# zx80_SD_12_smd_build006_1_STM32.net
KiCad netlist of a schematic drawn in EAGLE
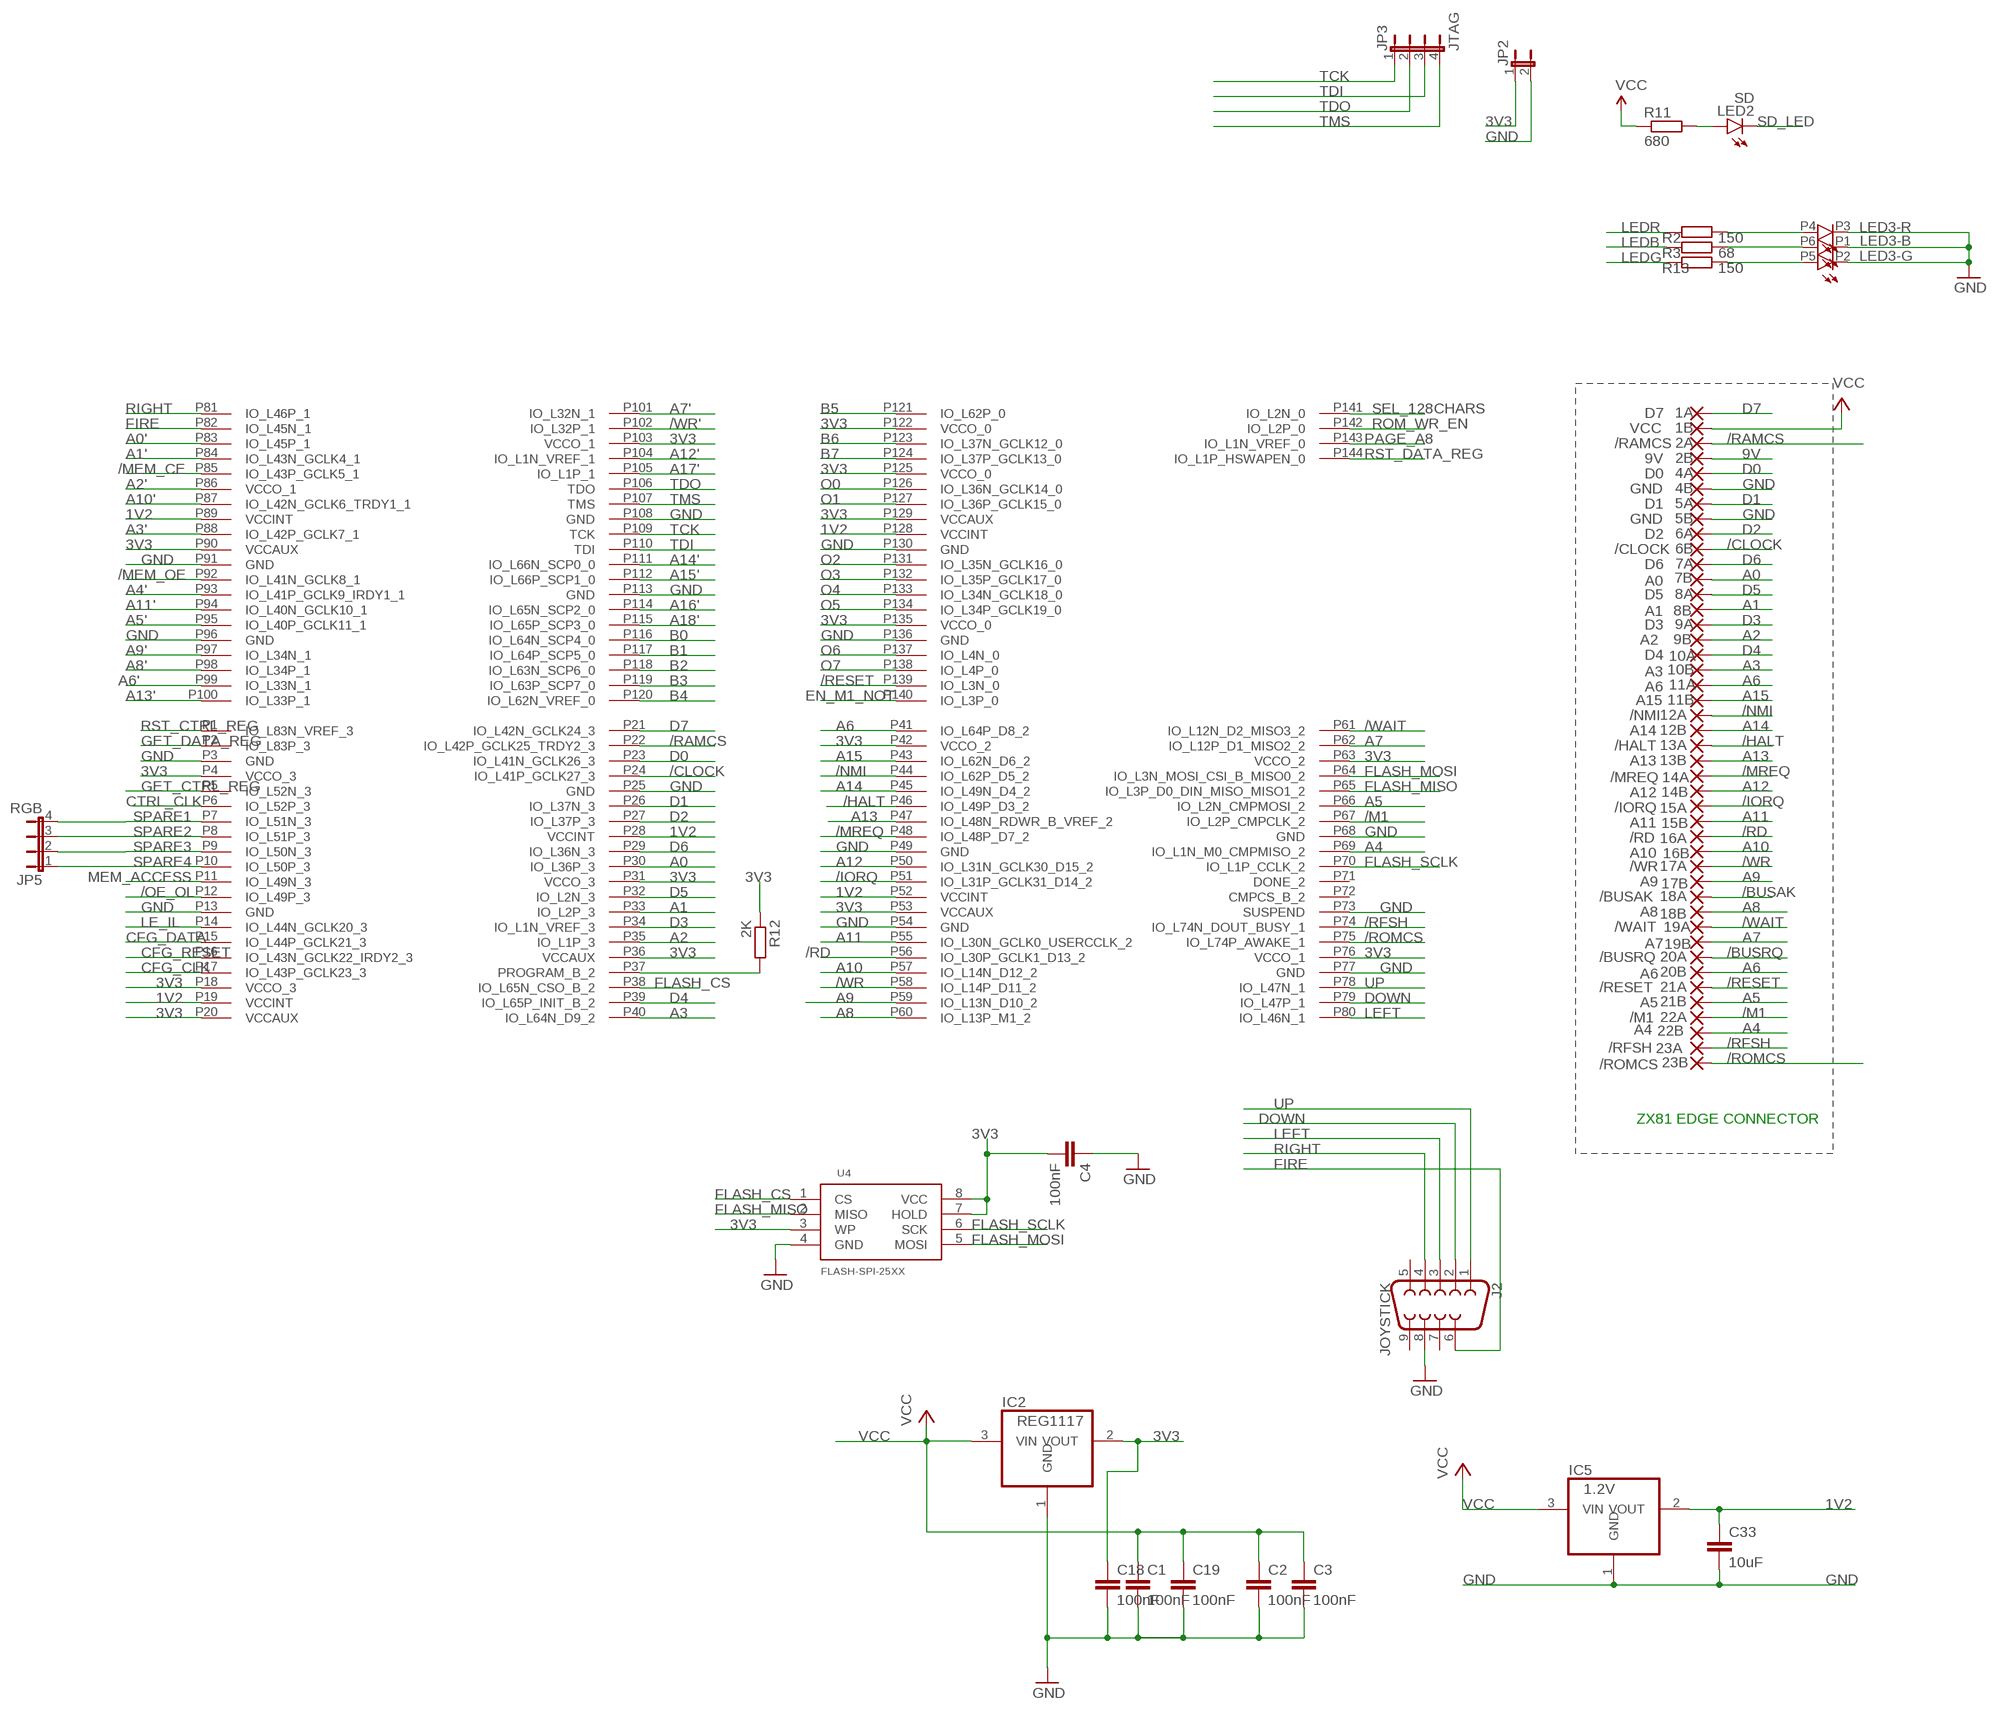
[diagram p0: schematic, sheet 1, part 1 of 2]
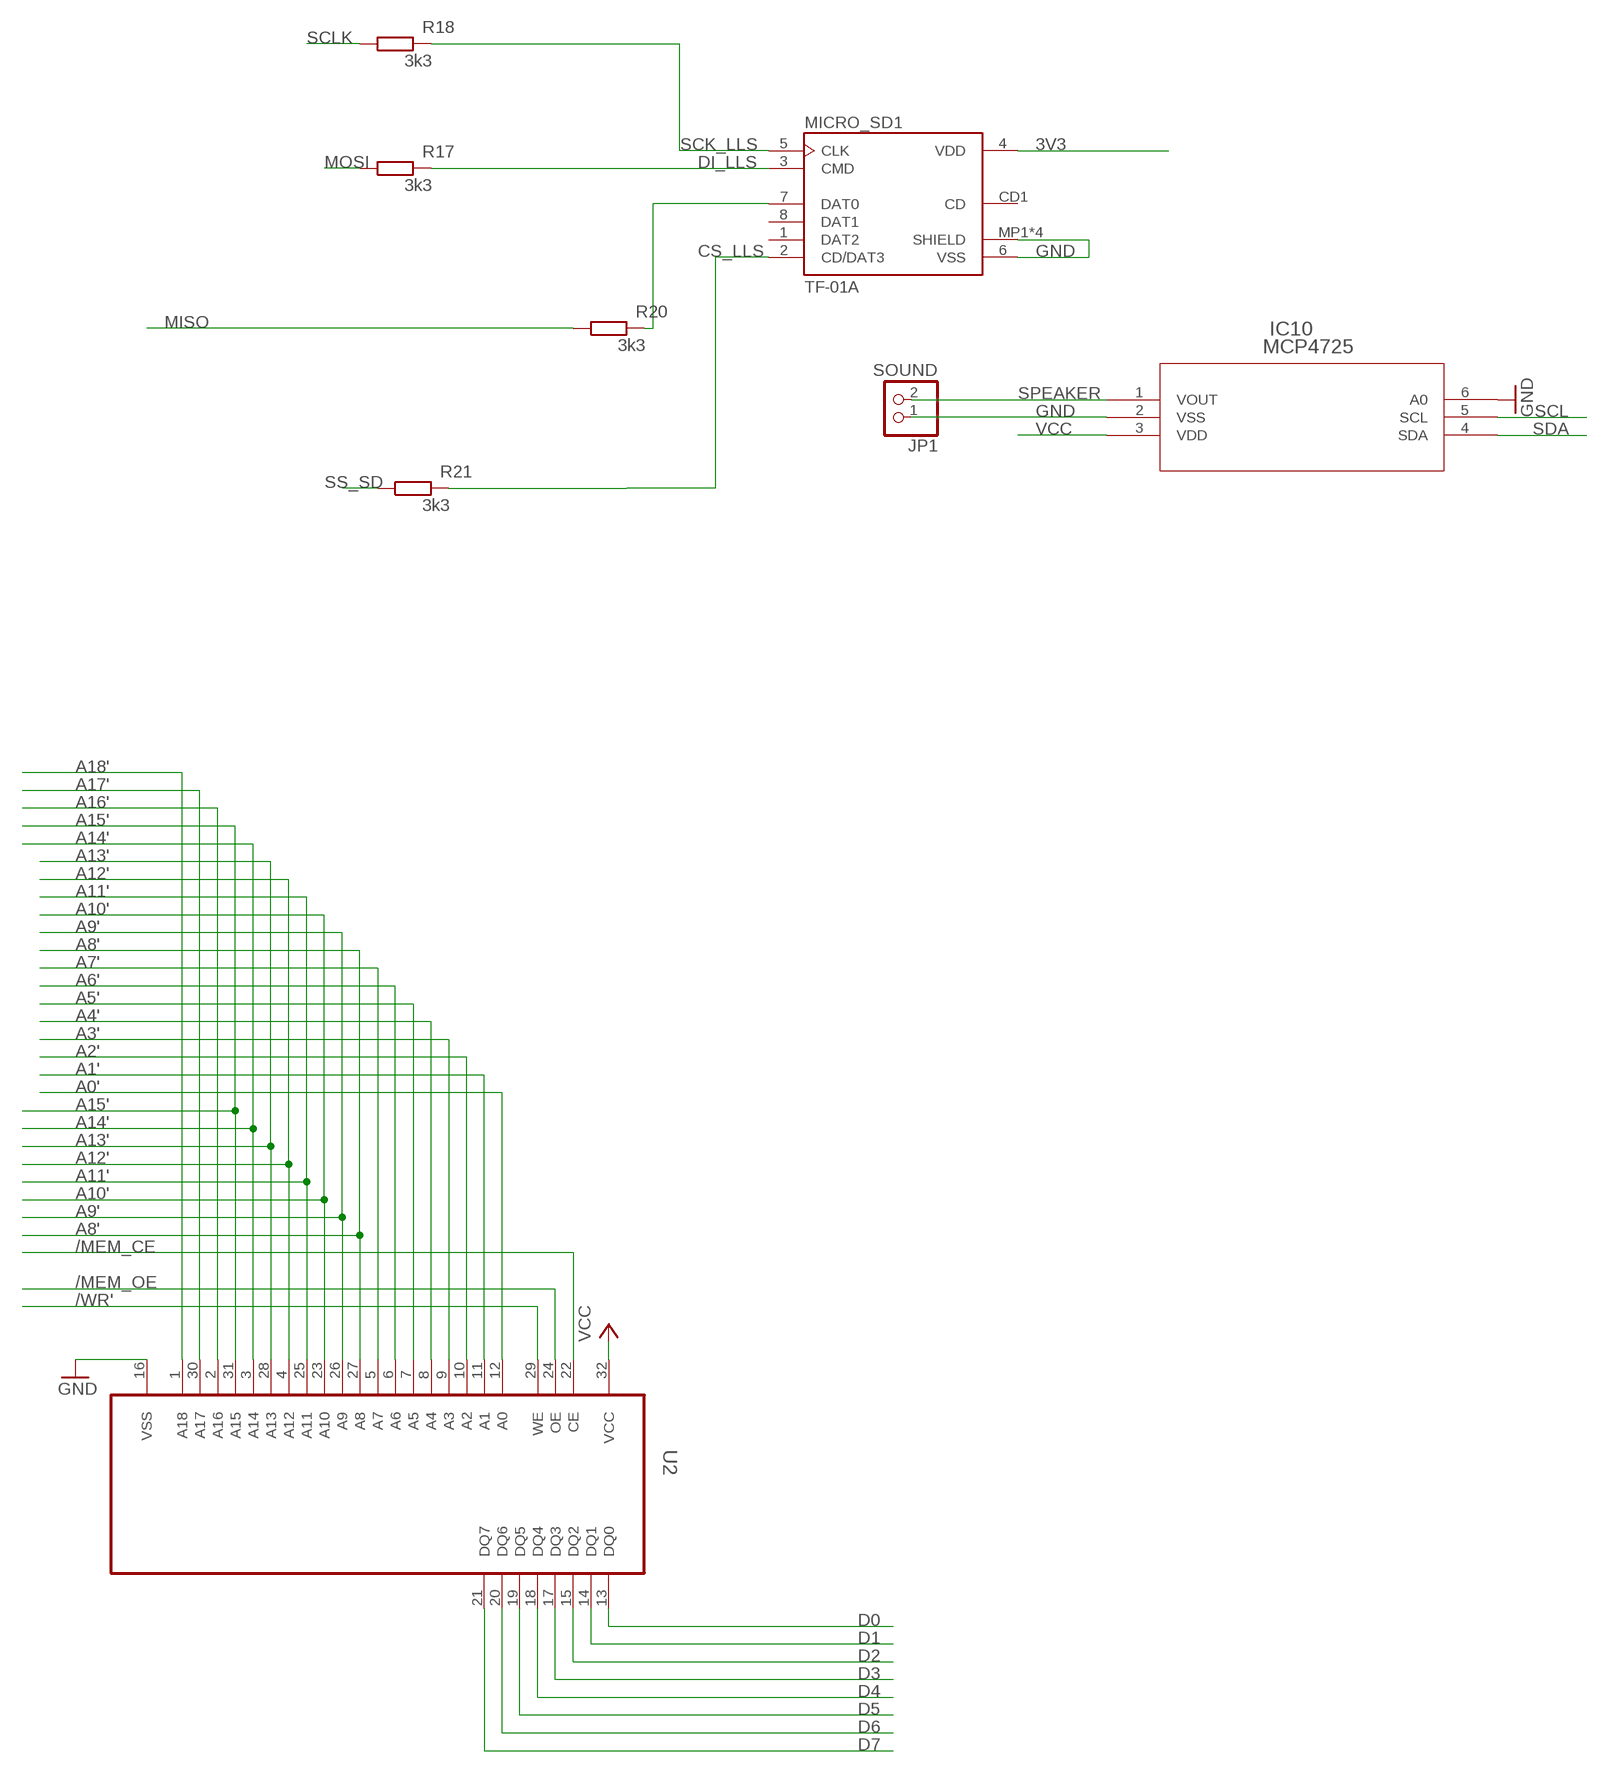
[diagram p1: schematic, sheet 1, part 2 of 2]
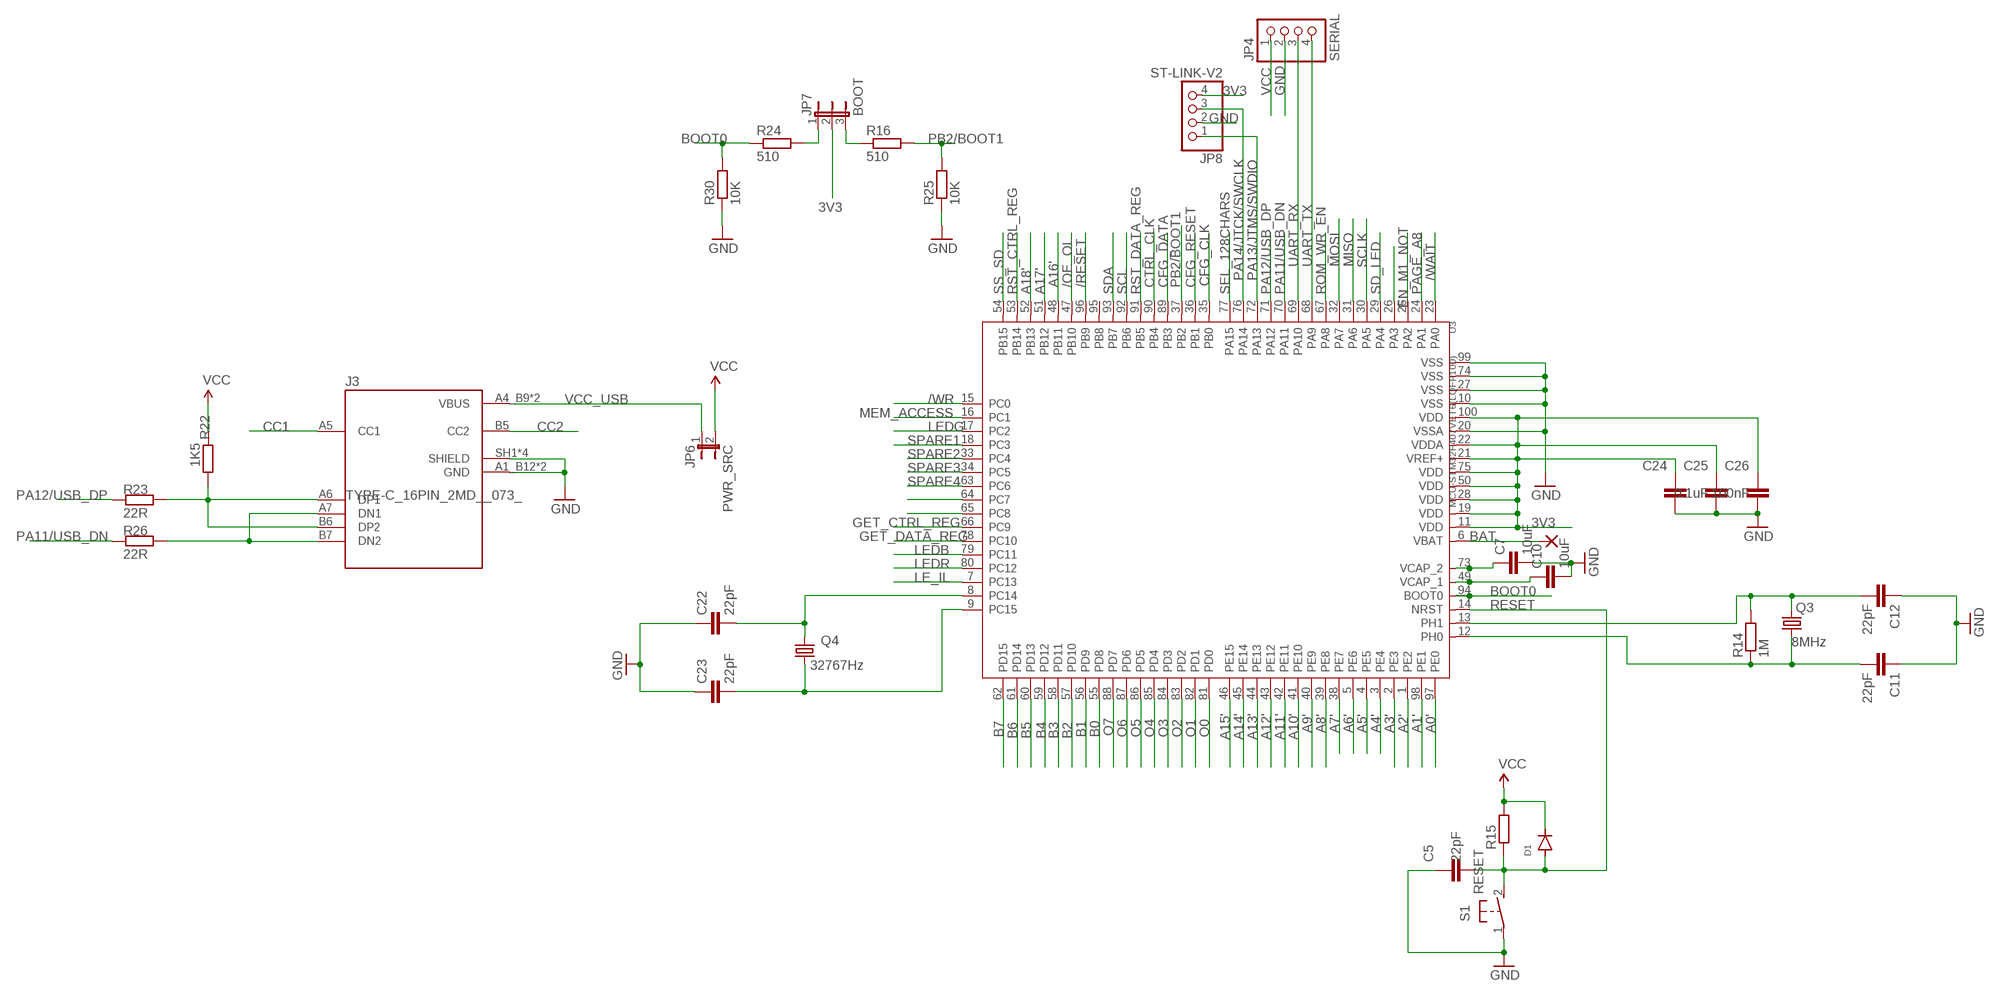
[diagram p2: schematic, sheet 2]

(export (version "E")
  (design (tool "Eeschema 10.0.6"))
  (components
    (comp (ref "BAT")
      (value "1,6/0,8")
      (footprint "eagle-import:1,6_0,8")
      (libsource (lib "eagle-import") (part "1,6/0,8"))
    )
    (comp (ref "C5")
      (value "22pF")
      (footprint "eagle-import:C0603")
      (libsource (lib "eagle-import") (part "rcl_334_C-EUC0603"))
    )
    (comp (ref "C7")
      (value "10uF")
      (footprint "eagle-import:C1206")
      (libsource (lib "eagle-import") (part "rcl_334_C-EUC1206"))
    )
    (comp (ref "C10")
      (value "10uF")
      (footprint "eagle-import:C1206")
      (libsource (lib "eagle-import") (part "rcl_334_C-EUC1206"))
    )
    (comp (ref "C11")
      (value "22pF")
      (footprint "eagle-import:C0603")
      (libsource (lib "eagle-import") (part "rcl_334_C-EUC0603"))
    )
    (comp (ref "C12")
      (value "22pF")
      (footprint "eagle-import:C0603")
      (libsource (lib "eagle-import") (part "rcl_334_C-EUC0603"))
    )
    (comp (ref "C22")
      (value "22pF")
      (footprint "eagle-import:C0603")
      (libsource (lib "eagle-import") (part "rcl_334_C-EUC0603"))
    )
    (comp (ref "C23")
      (value "22pF")
      (footprint "eagle-import:C0603")
      (libsource (lib "eagle-import") (part "rcl_334_C-EUC0603"))
    )
    (comp (ref "C24")
      (value "0.1uF")
      (footprint "eagle-import:C0603")
      (libsource (lib "eagle-import") (part "rcl_334_C-EUC0603"))
    )
    (comp (ref "C25")
      (value "0.1uF")
      (footprint "eagle-import:C0603")
      (libsource (lib "eagle-import") (part "rcl_334_C-EUC0603"))
    )
    (comp (ref "C26")
      (value "100nF")
      (footprint "eagle-import:C0603")
      (libsource (lib "eagle-import") (part "rcl_334_C-EUC0603"))
    )
    (comp (ref "D1")
      (value "DIODE-SOD123")
      (footprint "eagle-import:SOD123")
      (libsource (lib "eagle-import") (part "DIODE-SOD123"))
    )
    (comp (ref "J3")
      (value "TYPE-C_16PIN_2MD__073_")
      (footprint "eagle-import:SHOUHAN_TYPE-C_16PIN_2MD__073_")
      (fields (field (name "MF") "Shouhan") (field (name "MP") "TYPE-C 16PIN 2MD (073)"))
      (libsource (lib "eagle-import") (part "TYPE-C_16PIN_2MD__073_"))
    )
    (comp (ref "JP4")
      (value "SERIAL")
      (footprint "eagle-import:1X04")
      (libsource (lib "eagle-import") (part "PINHD-1X4"))
    )
    (comp (ref "JP6")
      (value "PWR_SRC")
      (footprint "eagle-import:HDRV2W64P254_2X1_300X350X838B")
      (libsource (lib "eagle-import") (part "JP1EJP13D"))
    )
    (comp (ref "JP7")
      (value "BOOT")
      (footprint "eagle-import:HDRV3W64P254_3X1_300X654X838B")
      (libsource (lib "eagle-import") (part "JP2EJP23D"))
    )
    (comp (ref "JP8")
      (value "ST-LINK-V2")
      (footprint "eagle-import:1X04")
      (libsource (lib "eagle-import") (part "PINHD-1X4"))
    )
    (comp (ref "Q3")
      (value "8MHz")
      (footprint "eagle-import:3.2X2.5_KX-7")
      (libsource (lib "eagle-import") (part "KX-7"))
    )
    (comp (ref "Q4")
      (value "32767Hz")
      (footprint "eagle-import:3.2X1.5")
      (libsource (lib "eagle-import") (part "KX-327-NHT"))
    )
    (comp (ref "R14")
      (value "1M")
      (footprint "eagle-import:R0603")
      (libsource (lib "eagle-import") (part "rcl_334_R-EU_R0603"))
    )
    (comp (ref "R15")
      (value "R-EU_R0603")
      (footprint "eagle-import:R0603")
      (libsource (lib "eagle-import") (part "rcl_334_R-EU_R0603"))
    )
    (comp (ref "R16")
      (value "510")
      (footprint "eagle-import:R0603")
      (libsource (lib "eagle-import") (part "rcl_334_R-EU_R0603"))
    )
    (comp (ref "R22")
      (value "1K5")
      (footprint "eagle-import:R0603")
      (libsource (lib "eagle-import") (part "R-EU_R0603"))
    )
    (comp (ref "R23")
      (value "22R")
      (footprint "eagle-import:R0603")
      (libsource (lib "eagle-import") (part "R-EU_R0603"))
    )
    (comp (ref "R24")
      (value "510")
      (footprint "eagle-import:R0603")
      (libsource (lib "eagle-import") (part "rcl_334_R-EU_R0603"))
    )
    (comp (ref "R25")
      (value "10K")
      (footprint "eagle-import:R0603")
      (libsource (lib "eagle-import") (part "rcl_334_R-EU_R0603"))
    )
    (comp (ref "R26")
      (value "22R")
      (footprint "eagle-import:R0603")
      (libsource (lib "eagle-import") (part "R-EU_R0603"))
    )
    (comp (ref "R30")
      (value "10K")
      (footprint "eagle-import:R0603")
      (libsource (lib "eagle-import") (part "rcl_334_R-EU_R0603"))
    )
    (comp (ref "S1")
      (value "RESET")
      (footprint "eagle-import:B3F-31XX")
      (fields (field (name "MPN") "B3F-3100"))
      (libsource (lib "eagle-import") (part "31-XX"))
    )
    (comp (ref "U3")
      (value "MCU-STM32F407VET6(LQFP100)")
      (footprint "eagle-import:LQFP100-0.5-13.8X13.8MM")
      (fields (field (name "MF") "STMicroelectronics") (field (name "MP") "STM32F407VET6"))
      (libsource (lib "eagle-import") (part "MCU-STM32F407VET6(LQFP100)"))
    )
    (comp (ref "1A")
      (value "D7")
      (footprint "eagle-import:EDGEPIN")
      (libsource (lib "eagle-import") (part "SMD2EDGEPIN"))
    )
    (comp (ref "1B")
      (value "VCC")
      (footprint "eagle-import:EDGEPIN")
      (libsource (lib "eagle-import") (part "SMD2EDGEPIN"))
    )
    (comp (ref "2A")
      (value "/RAMCS")
      (footprint "eagle-import:EDGEPIN")
      (libsource (lib "eagle-import") (part "SMD2EDGEPIN"))
    )
    (comp (ref "2B")
      (value "9V")
      (footprint "eagle-import:EDGEPIN")
      (libsource (lib "eagle-import") (part "SMD2EDGEPIN"))
    )
    (comp (ref "4A")
      (value "D0")
      (footprint "eagle-import:EDGEPIN")
      (libsource (lib "eagle-import") (part "SMD2EDGEPIN"))
    )
    (comp (ref "4B")
      (value "GND")
      (footprint "eagle-import:EDGEPIN")
      (libsource (lib "eagle-import") (part "SMD2EDGEPIN"))
    )
    (comp (ref "5A")
      (value "D1")
      (footprint "eagle-import:EDGEPIN")
      (libsource (lib "eagle-import") (part "SMD2EDGEPIN"))
    )
    (comp (ref "5B")
      (value "GND")
      (footprint "eagle-import:EDGEPIN")
      (libsource (lib "eagle-import") (part "SMD2EDGEPIN"))
    )
    (comp (ref "6A")
      (value "D2")
      (footprint "eagle-import:EDGEPIN")
      (libsource (lib "eagle-import") (part "SMD2EDGEPIN"))
    )
    (comp (ref "6B")
      (value "/CLOCK")
      (footprint "eagle-import:EDGEPIN")
      (libsource (lib "eagle-import") (part "SMD2EDGEPIN"))
    )
    (comp (ref "7A")
      (value "D6")
      (footprint "eagle-import:EDGEPIN")
      (libsource (lib "eagle-import") (part "SMD2EDGEPIN"))
    )
    (comp (ref "7B")
      (value "A0")
      (footprint "eagle-import:EDGEPIN")
      (libsource (lib "eagle-import") (part "SMD2EDGEPIN"))
    )
    (comp (ref "8A")
      (value "D5")
      (footprint "eagle-import:EDGEPIN")
      (libsource (lib "eagle-import") (part "SMD2EDGEPIN"))
    )
    (comp (ref "8B")
      (value "A1")
      (footprint "eagle-import:EDGEPIN")
      (libsource (lib "eagle-import") (part "SMD2EDGEPIN"))
    )
    (comp (ref "9A")
      (value "D3")
      (footprint "eagle-import:EDGEPIN")
      (libsource (lib "eagle-import") (part "SMD2EDGEPIN"))
    )
    (comp (ref "9B")
      (value "A2")
      (footprint "eagle-import:EDGEPIN")
      (libsource (lib "eagle-import") (part "SMD2EDGEPIN"))
    )
    (comp (ref "10A")
      (value "D4")
      (footprint "eagle-import:EDGEPIN")
      (libsource (lib "eagle-import") (part "SMD2EDGEPIN"))
    )
    (comp (ref "10B")
      (value "A3")
      (footprint "eagle-import:EDGEPIN")
      (libsource (lib "eagle-import") (part "SMD2EDGEPIN"))
    )
    (comp (ref "11A")
      (value "A6")
      (footprint "eagle-import:EDGEPIN")
      (libsource (lib "eagle-import") (part "SMD2EDGEPIN"))
    )
    (comp (ref "11B")
      (value "A15")
      (footprint "eagle-import:EDGEPIN")
      (libsource (lib "eagle-import") (part "SMD2EDGEPIN"))
    )
    (comp (ref "12A")
      (value "/NMI")
      (footprint "eagle-import:EDGEPIN")
      (libsource (lib "eagle-import") (part "SMD2EDGEPIN"))
    )
    (comp (ref "12B")
      (value "A14")
      (footprint "eagle-import:EDGEPIN")
      (libsource (lib "eagle-import") (part "SMD2EDGEPIN"))
    )
    (comp (ref "13A")
      (value "/HALT")
      (footprint "eagle-import:EDGEPIN")
      (libsource (lib "eagle-import") (part "SMD2EDGEPIN"))
    )
    (comp (ref "13B")
      (value "A13")
      (footprint "eagle-import:EDGEPIN")
      (libsource (lib "eagle-import") (part "SMD2EDGEPIN"))
    )
    (comp (ref "14A")
      (value "/MREQ")
      (footprint "eagle-import:EDGEPIN")
      (libsource (lib "eagle-import") (part "SMD2EDGEPIN"))
    )
    (comp (ref "14B")
      (value "A12")
      (footprint "eagle-import:EDGEPIN")
      (libsource (lib "eagle-import") (part "SMD2EDGEPIN"))
    )
    (comp (ref "15A")
      (value "/IORQ")
      (footprint "eagle-import:EDGEPIN")
      (libsource (lib "eagle-import") (part "SMD2EDGEPIN"))
    )
    (comp (ref "15B")
      (value "A11")
      (footprint "eagle-import:EDGEPIN")
      (libsource (lib "eagle-import") (part "SMD2EDGEPIN"))
    )
    (comp (ref "16A")
      (value "/RD")
      (footprint "eagle-import:EDGEPIN")
      (libsource (lib "eagle-import") (part "SMD2EDGEPIN"))
    )
    (comp (ref "16B")
      (value "A10")
      (footprint "eagle-import:EDGEPIN")
      (libsource (lib "eagle-import") (part "SMD2EDGEPIN"))
    )
    (comp (ref "17A")
      (value "/WR")
      (footprint "eagle-import:EDGEPIN")
      (libsource (lib "eagle-import") (part "SMD2EDGEPIN"))
    )
    (comp (ref "17B")
      (value "A9")
      (footprint "eagle-import:EDGEPIN")
      (libsource (lib "eagle-import") (part "SMD2EDGEPIN"))
    )
    (comp (ref "18A")
      (value "/BUSAK")
      (footprint "eagle-import:EDGEPIN")
      (libsource (lib "eagle-import") (part "SMD2EDGEPIN"))
    )
    (comp (ref "18B")
      (value "A8")
      (footprint "eagle-import:EDGEPIN")
      (libsource (lib "eagle-import") (part "SMD2EDGEPIN"))
    )
    (comp (ref "19A")
      (value "/WAIT")
      (footprint "eagle-import:EDGEPIN")
      (libsource (lib "eagle-import") (part "SMD2EDGEPIN"))
    )
    (comp (ref "19B")
      (value "A7")
      (footprint "eagle-import:EDGEPIN")
      (libsource (lib "eagle-import") (part "SMD2EDGEPIN"))
    )
    (comp (ref "20A")
      (value "/BUSRQ")
      (footprint "eagle-import:EDGEPIN")
      (libsource (lib "eagle-import") (part "SMD2EDGEPIN"))
    )
    (comp (ref "20B")
      (value "A6")
      (footprint "eagle-import:EDGEPIN")
      (libsource (lib "eagle-import") (part "SMD2EDGEPIN"))
    )
    (comp (ref "21A")
      (value "/RESET")
      (footprint "eagle-import:EDGEPIN")
      (libsource (lib "eagle-import") (part "SMD2EDGEPIN"))
    )
    (comp (ref "21B")
      (value "A5")
      (footprint "eagle-import:EDGEPIN")
      (libsource (lib "eagle-import") (part "SMD2EDGEPIN"))
    )
    (comp (ref "22A")
      (value "/M1")
      (footprint "eagle-import:EDGEPIN")
      (libsource (lib "eagle-import") (part "SMD2EDGEPIN"))
    )
    (comp (ref "22B")
      (value "A4")
      (footprint "eagle-import:EDGEPIN")
      (libsource (lib "eagle-import") (part "SMD2EDGEPIN"))
    )
    (comp (ref "23A")
      (value "/RFSH")
      (footprint "eagle-import:EDGEPIN")
      (libsource (lib "eagle-import") (part "SMD2EDGEPIN"))
    )
    (comp (ref "23B")
      (value "/ROMCS")
      (footprint "eagle-import:EDGEPIN")
      (libsource (lib "eagle-import") (part "SMD2EDGEPIN"))
    )
    (comp (ref "C1")
      (value "100nF")
      (footprint "eagle-import:C0603")
      (libsource (lib "eagle-import") (part "rcl_334_C-EUC0603"))
    )
    (comp (ref "C2")
      (value "100nF")
      (footprint "eagle-import:C0603")
      (libsource (lib "eagle-import") (part "rcl_334_C-EUC0603"))
    )
    (comp (ref "C3")
      (value "100nF")
      (footprint "eagle-import:C0603")
      (libsource (lib "eagle-import") (part "rcl_334_C-EUC0603"))
    )
    (comp (ref "C4")
      (value "100nF")
      (footprint "eagle-import:C0603K")
      (libsource (lib "eagle-import") (part "C-EUC0603K"))
    )
    (comp (ref "C18")
      (value "100nF")
      (footprint "eagle-import:C0603")
      (libsource (lib "eagle-import") (part "rcl_334_C-EUC0603"))
    )
    (comp (ref "C19")
      (value "100nF")
      (footprint "eagle-import:C0603")
      (libsource (lib "eagle-import") (part "rcl_334_C-EUC0603"))
    )
    (comp (ref "C33")
      (value "10uF")
      (footprint "eagle-import:C0603K")
      (libsource (lib "eagle-import") (part "C-EUC0603K"))
    )
    (comp (ref "IC2")
      (value "REG1117")
      (footprint "eagle-import:SOT223")
      (libsource (lib "eagle-import") (part "burr-brown_41243815_REG1117"))
    )
    (comp (ref "IC5")
      (value "1.2V")
      (footprint "eagle-import:SOT223")
      (fields (field (name "MPN") "REG1117"))
      (libsource (lib "eagle-import") (part "REG1117"))
    )
    (comp (ref "IC10")
      (value "MCP4725")
      (footprint "eagle-import:SOT-23-6_MC")
      (fields (field (name "MF") "Microchip") (field (name "MP") "MCP4725A2T-E/CH"))
      (libsource (lib "eagle-import") (part "MCP4725A2T-E/CH"))
    )
    (comp (ref "J2")
      (value "JOYSTICK")
      (footprint "eagle-import:DB9_MALE")
      (libsource (lib "eagle-import") (part "DB9MALE"))
    )
    (comp (ref "JP1")
      (value "SOUND")
      (footprint "eagle-import:1X02")
      (libsource (lib "eagle-import") (part "PINHD-1X2"))
    )
    (comp (ref "JP2")
      (value "JP1E")
      (footprint "eagle-import:JP1")
      (libsource (lib "eagle-import") (part "JP1E"))
    )
    (comp (ref "JP3")
      (value "JTAG")
      (footprint "eagle-import:JP4")
      (libsource (lib "eagle-import") (part "JP4E"))
    )
    (comp (ref "JP5")
      (value "RGB")
      (footprint "eagle-import:JP4")
      (libsource (lib "eagle-import") (part "JP4E"))
    )
    (comp (ref "LED2")
      (value "SD")
      (footprint "eagle-import:CHIPLED_0603")
      (libsource (lib "eagle-import") (part "LEDCHIPLED_0603"))
    )
    (comp (ref "LED3")
      (value "STATUS")
      (footprint "eagle-import:3535-PLCC6")
      (libsource (lib "eagle-import") (part "3535RGB3535RGB"))
    )
    (comp (ref "MICRO_SD1")
      (value "TF-01A")
      (footprint "eagle-import:TF-01A")
      (fields (field (name "MF") "HRO Electronics Co., Ltd."))
      (libsource (lib "eagle-import") (part "TF-01A"))
    )
    (comp (ref "R2")
      (value "150")
      (footprint "eagle-import:R0603")
      (libsource (lib "eagle-import") (part "rcl_334_R-EU_R0603"))
    )
    (comp (ref "R3")
      (value "68")
      (footprint "eagle-import:R0603")
      (libsource (lib "eagle-import") (part "rcl_334_R-EU_R0603"))
    )
    (comp (ref "R11")
      (value "680")
      (footprint "eagle-import:R0603")
      (libsource (lib "eagle-import") (part "R-EU_R0603"))
    )
    (comp (ref "R12")
      (value "2K")
      (footprint "eagle-import:R0603")
      (libsource (lib "eagle-import") (part "rcl_334_R-EU_R0603"))
    )
    (comp (ref "R13")
      (value "150")
      (footprint "eagle-import:R0603")
      (libsource (lib "eagle-import") (part "rcl_334_R-EU_R0603"))
    )
    (comp (ref "R17")
      (value "3k3")
      (footprint "eagle-import:R0603")
      (libsource (lib "eagle-import") (part "R-EU_R0603"))
    )
    (comp (ref "R18")
      (value "3k3")
      (footprint "eagle-import:R0603")
      (libsource (lib "eagle-import") (part "R-EU_R0603"))
    )
    (comp (ref "R20")
      (value "3k3")
      (footprint "eagle-import:R0603")
      (libsource (lib "eagle-import") (part "R-EU_R0603"))
    )
    (comp (ref "R21")
      (value "3k3")
      (footprint "eagle-import:R0603")
      (libsource (lib "eagle-import") (part "R-EU_R0603"))
    )
    (comp (ref "U$1")
      (value "XC6SLX9-2TQG144C")
      (footprint "eagle-import:TQ144")
      (fields (field (name "MF") "Xilinx Inc."))
      (libsource (lib "eagle-import") (part "XC6SLX9-2TQG144C"))
    )
    (comp (ref "U2")
      (value "AS6C4008")
      (footprint "eagle-import:SOP32-5")
      (libsource (lib "eagle-import") (part "AS6C4008-55SINSOP5"))
    )
    (comp (ref "U4")
      (value "FLASH-SPI-25XX")
      (footprint "eagle-import:SO08-EIAJ")
      (libsource (lib "eagle-import") (part "FLASH-SPI-25XXSMD1"))
    )
  )
  (nets
    (net (code "1") (name "1V2") (class "Default")
      (node (ref "C33") (pin "1") (pinfunction "1_1") (pintype "passive"))
      (node (ref "IC5") (pin "2") (pinfunction "VOUT_2") (pintype "output"))
      (node (ref "U$1") (pin "P128") (pinfunction "VCCINT_P128") (pintype "bidirectional"))
      (node (ref "U$1") (pin "P19") (pinfunction "VCCINT_P19") (pintype "bidirectional"))
      (node (ref "U$1") (pin "P28") (pinfunction "VCCINT_P28") (pintype "bidirectional"))
      (node (ref "U$1") (pin "P52") (pinfunction "VCCINT_P52") (pintype "bidirectional"))
      (node (ref "U$1") (pin "P89") (pinfunction "VCCINT_P89") (pintype "bidirectional"))
    )
    (net (code "2") (name "3V3") (class "Default")
      (node (ref "C18") (pin "1") (pinfunction "1_1") (pintype "passive"))
      (node (ref "C24") (pin "1") (pinfunction "1_1") (pintype "passive"))
      (node (ref "C25") (pin "1") (pinfunction "1_1") (pintype "passive"))
      (node (ref "C26") (pin "1") (pinfunction "1_1") (pintype "passive"))
      (node (ref "C4") (pin "2") (pinfunction "2_2") (pintype "passive"))
      (node (ref "IC2") (pin "2") (pinfunction "VOUT_2") (pintype "output"))
      (node (ref "JP2") (pin "1") (pinfunction "1_1") (pintype "passive"))
      (node (ref "JP7") (pin "2") (pinfunction "2_2") (pintype "passive"))
      (node (ref "JP8") (pin "4") (pinfunction "4_4") (pintype "passive"))
      (node (ref "MICRO_SD1") (pin "4") (pinfunction "VDD_4") (pintype "power_in"))
      (node (ref "R12") (pin "1") (pinfunction "1_1") (pintype "passive"))
      (node (ref "U$1") (pin "P103") (pinfunction "VCCO_1_P103") (pintype "bidirectional"))
      (node (ref "U$1") (pin "P122") (pinfunction "VCCO_0_P122") (pintype "bidirectional"))
      (node (ref "U$1") (pin "P125") (pinfunction "VCCO_0_P125") (pintype "bidirectional"))
      (node (ref "U$1") (pin "P129") (pinfunction "VCCAUX_P129") (pintype "bidirectional"))
      (node (ref "U$1") (pin "P135") (pinfunction "VCCO_0_P135") (pintype "bidirectional"))
      (node (ref "U$1") (pin "P18") (pinfunction "VCCO_3_P18") (pintype "bidirectional"))
      (node (ref "U$1") (pin "P20") (pinfunction "VCCAUX_P20") (pintype "bidirectional"))
      (node (ref "U$1") (pin "P31") (pinfunction "VCCO_3_P31") (pintype "bidirectional"))
      (node (ref "U$1") (pin "P36") (pinfunction "VCCAUX_P36") (pintype "bidirectional"))
      (node (ref "U$1") (pin "P4") (pinfunction "VCCO_3_P4") (pintype "bidirectional"))
      (node (ref "U$1") (pin "P42") (pinfunction "VCCO_2_P42") (pintype "bidirectional"))
      (node (ref "U$1") (pin "P53") (pinfunction "VCCAUX_P53") (pintype "bidirectional"))
      (node (ref "U$1") (pin "P63") (pinfunction "VCCO_2_P63") (pintype "bidirectional"))
      (node (ref "U$1") (pin "P76") (pinfunction "VCCO_1_P76") (pintype "bidirectional"))
      (node (ref "U$1") (pin "P90") (pinfunction "VCCAUX_P90") (pintype "bidirectional"))
      (node (ref "U3") (pin "100") (pinfunction "VDD_100") (pintype "bidirectional"))
      (node (ref "U3") (pin "11") (pinfunction "VDD_11") (pintype "bidirectional"))
      (node (ref "U3") (pin "19") (pinfunction "VDD_19") (pintype "bidirectional"))
      (node (ref "U3") (pin "21") (pinfunction "VREF+_21") (pintype "bidirectional"))
      (node (ref "U3") (pin "22") (pinfunction "VDDA_22") (pintype "bidirectional"))
      (node (ref "U3") (pin "28") (pinfunction "VDD_28") (pintype "bidirectional"))
      (node (ref "U3") (pin "50") (pinfunction "VDD_50") (pintype "bidirectional"))
      (node (ref "U3") (pin "75") (pinfunction "VDD_75") (pintype "bidirectional"))
      (node (ref "U4") (pin "3") (pinfunction "WP_3") (pintype "bidirectional"))
      (node (ref "U4") (pin "7") (pinfunction "HOLD_7") (pintype "bidirectional"))
      (node (ref "U4") (pin "8") (pinfunction "VCC_8") (pintype "bidirectional"))
    )
    (net (code "3") (name "9V") (class "Default")
      (node (ref "2B") (pin "1") (pinfunction "P_1") (pintype "passive"))
    )
    (net (code "4") (name "A0") (class "Default")
      (node (ref "7B") (pin "1") (pinfunction "P_1") (pintype "passive"))
      (node (ref "U$1") (pin "P30") (pinfunction "IO_L36P_3_P30") (pintype "bidirectional"))
    )
    (net (code "5") (name "A0'") (class "Default")
      (node (ref "U$1") (pin "P83") (pinfunction "IO_L45P_1_P83") (pintype "bidirectional"))
      (node (ref "U2") (pin "12") (pinfunction "A0_12") (pintype "input"))
      (node (ref "U3") (pin "97") (pinfunction "PE0_97") (pintype "bidirectional"))
    )
    (net (code "6") (name "A1") (class "Default")
      (node (ref "8B") (pin "1") (pinfunction "P_1") (pintype "passive"))
      (node (ref "U$1") (pin "P33") (pinfunction "IO_L2P_3_P33") (pintype "bidirectional"))
    )
    (net (code "7") (name "A1'") (class "Default")
      (node (ref "U$1") (pin "P84") (pinfunction "IO_L43N_GCLK4_1_P84") (pintype "bidirectional"))
      (node (ref "U2") (pin "11") (pinfunction "A1_11") (pintype "input"))
      (node (ref "U3") (pin "98") (pinfunction "PE1_98") (pintype "bidirectional"))
    )
    (net (code "8") (name "A2") (class "Default")
      (node (ref "9B") (pin "1") (pinfunction "P_1") (pintype "passive"))
      (node (ref "U$1") (pin "P35") (pinfunction "IO_L1P_3_P35") (pintype "bidirectional"))
    )
    (net (code "9") (name "A2'") (class "Default")
      (node (ref "U$1") (pin "P86") (pinfunction "VCCO_1_P86") (pintype "bidirectional"))
      (node (ref "U2") (pin "10") (pinfunction "A2_10") (pintype "input"))
      (node (ref "U3") (pin "1") (pinfunction "PE2_1") (pintype "bidirectional"))
    )
    (net (code "10") (name "A3") (class "Default")
      (node (ref "10B") (pin "1") (pinfunction "P_1") (pintype "passive"))
      (node (ref "U$1") (pin "P40") (pinfunction "IO_L64N_D9_2_P40") (pintype "bidirectional"))
    )
    (net (code "11") (name "A3'") (class "Default")
      (node (ref "U$1") (pin "P88") (pinfunction "IO_L42P_GCLK7_1_P88") (pintype "bidirectional"))
      (node (ref "U2") (pin "9") (pinfunction "A3_9") (pintype "input"))
      (node (ref "U3") (pin "2") (pinfunction "PE3_2") (pintype "bidirectional"))
    )
    (net (code "12") (name "A4") (class "Default")
      (node (ref "22B") (pin "1") (pinfunction "P_1") (pintype "passive"))
      (node (ref "U$1") (pin "P69") (pinfunction "IO_L1N_M0_CMPMISO_2_P69") (pintype "bidirectional"))
    )
    (net (code "13") (name "A4'") (class "Default")
      (node (ref "U$1") (pin "P93") (pinfunction "IO_L41P_GCLK9_IRDY1_1_P93") (pintype "bidirectional"))
      (node (ref "U2") (pin "8") (pinfunction "A4_8") (pintype "input"))
      (node (ref "U3") (pin "3") (pinfunction "PE4_3") (pintype "bidirectional"))
    )
    (net (code "14") (name "A5") (class "Default")
      (node (ref "21B") (pin "1") (pinfunction "P_1") (pintype "passive"))
      (node (ref "U$1") (pin "P66") (pinfunction "IO_L2N_CMPMOSI_2_P66") (pintype "bidirectional"))
    )
    (net (code "15") (name "A5'") (class "Default")
      (node (ref "U$1") (pin "P95") (pinfunction "IO_L40P_GCLK11_1_P95") (pintype "bidirectional"))
      (node (ref "U2") (pin "7") (pinfunction "A5_7") (pintype "input"))
      (node (ref "U3") (pin "4") (pinfunction "PE5_4") (pintype "bidirectional"))
    )
    (net (code "16") (name "A6") (class "Default")
      (node (ref "11A") (pin "1") (pinfunction "P_1") (pintype "passive"))
      (node (ref "20B") (pin "1") (pinfunction "P_1") (pintype "passive"))
      (node (ref "U$1") (pin "P41") (pinfunction "IO_L64P_D8_2_P41") (pintype "bidirectional"))
    )
    (net (code "17") (name "A6'") (class "Default")
      (node (ref "U$1") (pin "P99") (pinfunction "IO_L33N_1_P99") (pintype "bidirectional"))
      (node (ref "U2") (pin "6") (pinfunction "A6_6") (pintype "input"))
      (node (ref "U3") (pin "5") (pinfunction "PE6_5") (pintype "bidirectional"))
    )
    (net (code "18") (name "A7") (class "Default")
      (node (ref "19B") (pin "1") (pinfunction "P_1") (pintype "passive"))
      (node (ref "U$1") (pin "P62") (pinfunction "IO_L12P_D1_MISO2_2_P62") (pintype "bidirectional"))
    )
    (net (code "19") (name "A7'") (class "Default")
      (node (ref "U$1") (pin "P101") (pinfunction "IO_L32N_1_P101") (pintype "bidirectional"))
      (node (ref "U2") (pin "5") (pinfunction "A7_5") (pintype "input"))
      (node (ref "U3") (pin "38") (pinfunction "PE7_38") (pintype "bidirectional"))
    )
    (net (code "20") (name "A8") (class "Default")
      (node (ref "18B") (pin "1") (pinfunction "P_1") (pintype "passive"))
      (node (ref "U$1") (pin "P60") (pinfunction "IO_L13P_M1_2_P60") (pintype "bidirectional"))
    )
    (net (code "21") (name "A8'") (class "Default")
      (node (ref "U$1") (pin "P98") (pinfunction "IO_L34P_1_P98") (pintype "bidirectional"))
      (node (ref "U2") (pin "27") (pinfunction "A8_27") (pintype "input"))
      (node (ref "U3") (pin "39") (pinfunction "PE8_39") (pintype "bidirectional"))
    )
    (net (code "22") (name "A9") (class "Default")
      (node (ref "17B") (pin "1") (pinfunction "P_1") (pintype "passive"))
      (node (ref "U$1") (pin "P59") (pinfunction "IO_L13N_D10_2_P59") (pintype "bidirectional"))
    )
    (net (code "23") (name "A9'") (class "Default")
      (node (ref "U$1") (pin "P97") (pinfunction "IO_L34N_1_P97") (pintype "bidirectional"))
      (node (ref "U2") (pin "26") (pinfunction "A9_26") (pintype "input"))
      (node (ref "U3") (pin "40") (pinfunction "PE9_40") (pintype "bidirectional"))
    )
    (net (code "24") (name "A10") (class "Default")
      (node (ref "16B") (pin "1") (pinfunction "P_1") (pintype "passive"))
      (node (ref "U$1") (pin "P57") (pinfunction "IO_L14N_D12_2_P57") (pintype "bidirectional"))
    )
    (net (code "25") (name "A10'") (class "Default")
      (node (ref "U$1") (pin "P87") (pinfunction "IO_L42N_GCLK6_TRDY1_1_P87") (pintype "bidirectional"))
      (node (ref "U2") (pin "23") (pinfunction "A10_23") (pintype "input"))
      (node (ref "U3") (pin "41") (pinfunction "PE10_41") (pintype "bidirectional"))
    )
    (net (code "26") (name "A11") (class "Default")
      (node (ref "15B") (pin "1") (pinfunction "P_1") (pintype "passive"))
      (node (ref "U$1") (pin "P55") (pinfunction "IO_L30N_GCLK0_USERCCLK_2_P55") (pintype "bidirectional"))
    )
    (net (code "27") (name "A11'") (class "Default")
      (node (ref "U$1") (pin "P94") (pinfunction "IO_L40N_GCLK10_1_P94") (pintype "bidirectional"))
      (node (ref "U2") (pin "25") (pinfunction "A11_25") (pintype "input"))
      (node (ref "U3") (pin "42") (pinfunction "PE11_42") (pintype "bidirectional"))
    )
    (net (code "28") (name "A12") (class "Default")
      (node (ref "14B") (pin "1") (pinfunction "P_1") (pintype "passive"))
      (node (ref "U$1") (pin "P50") (pinfunction "IO_L31N_GCLK30_D15_2_P50") (pintype "bidirectional"))
    )
    (net (code "29") (name "A12'") (class "Default")
      (node (ref "U$1") (pin "P104") (pinfunction "IO_L1N_VREF_1_P104") (pintype "bidirectional"))
      (node (ref "U2") (pin "4") (pinfunction "A12_4") (pintype "input"))
      (node (ref "U3") (pin "43") (pinfunction "PE12_43") (pintype "bidirectional"))
    )
    (net (code "30") (name "A13") (class "Default")
      (node (ref "13B") (pin "1") (pinfunction "P_1") (pintype "passive"))
      (node (ref "U$1") (pin "P47") (pinfunction "IO_L48N_RDWR_B_VREF_2_P47") (pintype "bidirectional"))
    )
    (net (code "31") (name "A13'") (class "Default")
      (node (ref "U$1") (pin "P100") (pinfunction "IO_L33P_1_P100") (pintype "bidirectional"))
      (node (ref "U2") (pin "28") (pinfunction "A13_28") (pintype "input"))
      (node (ref "U3") (pin "44") (pinfunction "PE13_44") (pintype "bidirectional"))
    )
    (net (code "32") (name "A14") (class "Default")
      (node (ref "12B") (pin "1") (pinfunction "P_1") (pintype "passive"))
      (node (ref "U$1") (pin "P45") (pinfunction "IO_L49N_D4_2_P45") (pintype "bidirectional"))
    )
    (net (code "33") (name "A14'") (class "Default")
      (node (ref "U$1") (pin "P111") (pinfunction "IO_L66N_SCP0_0_P111") (pintype "bidirectional"))
      (node (ref "U2") (pin "3") (pinfunction "A14_3") (pintype "input"))
      (node (ref "U3") (pin "45") (pinfunction "PE14_45") (pintype "bidirectional"))
    )
    (net (code "34") (name "A15") (class "Default")
      (node (ref "11B") (pin "1") (pinfunction "P_1") (pintype "passive"))
      (node (ref "U$1") (pin "P43") (pinfunction "IO_L62N_D6_2_P43") (pintype "bidirectional"))
    )
    (net (code "35") (name "A15'") (class "Default")
      (node (ref "U$1") (pin "P112") (pinfunction "IO_L66P_SCP1_0_P112") (pintype "bidirectional"))
      (node (ref "U2") (pin "31") (pinfunction "A15_31") (pintype "input"))
      (node (ref "U3") (pin "46") (pinfunction "PE15_46") (pintype "bidirectional"))
    )
    (net (code "36") (name "A16'") (class "Default")
      (node (ref "U$1") (pin "P114") (pinfunction "IO_L65N_SCP2_0_P114") (pintype "bidirectional"))
      (node (ref "U2") (pin "2") (pinfunction "A16_2") (pintype "input"))
      (node (ref "U3") (pin "48") (pinfunction "PB11_48") (pintype "bidirectional"))
    )
    (net (code "37") (name "A17'") (class "Default")
      (node (ref "U$1") (pin "P105") (pinfunction "IO_L1P_1_P105") (pintype "bidirectional"))
      (node (ref "U2") (pin "30") (pinfunction "A17_30") (pintype "input"))
      (node (ref "U3") (pin "51") (pinfunction "PB12_51") (pintype "bidirectional"))
    )
    (net (code "38") (name "A18'") (class "Default")
      (node (ref "U$1") (pin "P115") (pinfunction "IO_L65P_SCP3_0_P115") (pintype "bidirectional"))
      (node (ref "U2") (pin "1") (pinfunction "A18_1") (pintype "input"))
      (node (ref "U3") (pin "52") (pinfunction "PB13_52") (pintype "bidirectional"))
    )
    (net (code "39") (name "B0") (class "Default")
      (node (ref "U$1") (pin "P116") (pinfunction "IO_L64N_SCP4_0_P116") (pintype "bidirectional"))
      (node (ref "U3") (pin "55") (pinfunction "PD8_55") (pintype "bidirectional"))
    )
    (net (code "40") (name "B1") (class "Default")
      (node (ref "U$1") (pin "P117") (pinfunction "IO_L64P_SCP5_0_P117") (pintype "bidirectional"))
      (node (ref "U3") (pin "56") (pinfunction "PD9_56") (pintype "bidirectional"))
    )
    (net (code "41") (name "B2") (class "Default")
      (node (ref "U$1") (pin "P118") (pinfunction "IO_L63N_SCP6_0_P118") (pintype "bidirectional"))
      (node (ref "U3") (pin "57") (pinfunction "PD10_57") (pintype "bidirectional"))
    )
    (net (code "42") (name "B3") (class "Default")
      (node (ref "U$1") (pin "P119") (pinfunction "IO_L63P_SCP7_0_P119") (pintype "bidirectional"))
      (node (ref "U3") (pin "58") (pinfunction "PD11_58") (pintype "bidirectional"))
    )
    (net (code "43") (name "B4") (class "Default")
      (node (ref "U$1") (pin "P120") (pinfunction "IO_L62N_VREF_0_P120") (pintype "bidirectional"))
      (node (ref "U3") (pin "59") (pinfunction "PD12_59") (pintype "bidirectional"))
    )
    (net (code "44") (name "B5") (class "Default")
      (node (ref "U$1") (pin "P121") (pinfunction "IO_L62P_0_P121") (pintype "bidirectional"))
      (node (ref "U3") (pin "60") (pinfunction "PD13_60") (pintype "bidirectional"))
    )
    (net (code "45") (name "B6") (class "Default")
      (node (ref "U$1") (pin "P123") (pinfunction "IO_L37N_GCLK12_0_P123") (pintype "bidirectional"))
      (node (ref "U3") (pin "61") (pinfunction "PD14_61") (pintype "bidirectional"))
    )
    (net (code "46") (name "B7") (class "Default")
      (node (ref "U$1") (pin "P124") (pinfunction "IO_L37P_GCLK13_0_P124") (pintype "bidirectional"))
      (node (ref "U3") (pin "62") (pinfunction "PD15_62") (pintype "bidirectional"))
    )
    (net (code "47") (name "BAT") (class "Default")
      (node (ref "BAT") (pin "1") (pinfunction "P_1") (pintype "passive"))
      (node (ref "U3") (pin "6") (pinfunction "VBAT_6") (pintype "bidirectional"))
    )
    (net (code "48") (name "BOOT0") (class "Default")
      (node (ref "R24") (pin "1") (pinfunction "1_1") (pintype "passive"))
      (node (ref "R30") (pin "2") (pinfunction "2_2") (pintype "passive"))
      (node (ref "U3") (pin "94") (pinfunction "BOOT0_94") (pintype "bidirectional"))
    )
    (net (code "49") (name "CC1") (class "Default")
      (node (ref "J3") (pin "A5") (pinfunction "CC1_A5") (pintype "bidirectional"))
    )
    (net (code "50") (name "CC2") (class "Default")
      (node (ref "J3") (pin "B5") (pinfunction "CC2_B5") (pintype "bidirectional"))
    )
    (net (code "51") (name "CFG_CLK") (class "Default")
      (node (ref "U$1") (pin "P17") (pinfunction "IO_L43P_GCLK23_3_P17") (pintype "bidirectional"))
      (node (ref "U3") (pin "35") (pinfunction "PB0_35") (pintype "bidirectional"))
    )
    (net (code "52") (name "CFG_DATA") (class "Default")
      (node (ref "U$1") (pin "P15") (pinfunction "IO_L44P_GCLK21_3_P15") (pintype "bidirectional"))
      (node (ref "U3") (pin "89") (pinfunction "PB3_89") (pintype "bidirectional"))
    )
    (net (code "53") (name "CFG_RESET") (class "Default")
      (node (ref "U$1") (pin "P16") (pinfunction "IO_L43N_GCLK22_IRDY2_3_P16") (pintype "bidirectional"))
      (node (ref "U3") (pin "36") (pinfunction "PB1_36") (pintype "bidirectional"))
    )
    (net (code "54") (name "CS_LLS") (class "Default")
      (node (ref "MICRO_SD1") (pin "2") (pinfunction "CD/DAT3_2") (pintype "bidirectional"))
      (node (ref "R21") (pin "2") (pinfunction "2_2") (pintype "passive"))
    )
    (net (code "55") (name "CTRL_CLK") (class "Default")
      (node (ref "U$1") (pin "P6") (pinfunction "IO_L52P_3_P6") (pintype "bidirectional"))
      (node (ref "U3") (pin "90") (pinfunction "PB4_90") (pintype "bidirectional"))
    )
    (net (code "56") (name "D0") (class "Default")
      (node (ref "4A") (pin "1") (pinfunction "P_1") (pintype "passive"))
      (node (ref "U$1") (pin "P23") (pinfunction "IO_L41N_GCLK26_3_P23") (pintype "bidirectional"))
      (node (ref "U2") (pin "13") (pinfunction "DQ0_13") (pintype "output"))
    )
    (net (code "57") (name "D1") (class "Default")
      (node (ref "5A") (pin "1") (pinfunction "P_1") (pintype "passive"))
      (node (ref "U$1") (pin "P26") (pinfunction "IO_L37N_3_P26") (pintype "bidirectional"))
      (node (ref "U2") (pin "14") (pinfunction "DQ1_14") (pintype "output"))
    )
    (net (code "58") (name "D2") (class "Default")
      (node (ref "6A") (pin "1") (pinfunction "P_1") (pintype "passive"))
      (node (ref "U$1") (pin "P27") (pinfunction "IO_L37P_3_P27") (pintype "bidirectional"))
      (node (ref "U2") (pin "15") (pinfunction "DQ2_15") (pintype "output"))
    )
    (net (code "59") (name "D3") (class "Default")
      (node (ref "9A") (pin "1") (pinfunction "P_1") (pintype "passive"))
      (node (ref "U$1") (pin "P34") (pinfunction "IO_L1N_VREF_3_P34") (pintype "bidirectional"))
      (node (ref "U2") (pin "17") (pinfunction "DQ3_17") (pintype "output"))
    )
    (net (code "60") (name "D4") (class "Default")
      (node (ref "10A") (pin "1") (pinfunction "P_1") (pintype "passive"))
      (node (ref "U$1") (pin "P39") (pinfunction "IO_L65P_INIT_B_2_P39") (pintype "bidirectional"))
      (node (ref "U2") (pin "18") (pinfunction "DQ4_18") (pintype "output"))
    )
    (net (code "61") (name "D5") (class "Default")
      (node (ref "8A") (pin "1") (pinfunction "P_1") (pintype "passive"))
      (node (ref "U$1") (pin "P32") (pinfunction "IO_L2N_3_P32") (pintype "bidirectional"))
      (node (ref "U2") (pin "19") (pinfunction "DQ5_19") (pintype "output"))
    )
    (net (code "62") (name "D6") (class "Default")
      (node (ref "7A") (pin "1") (pinfunction "P_1") (pintype "passive"))
      (node (ref "U$1") (pin "P29") (pinfunction "IO_L36N_3_P29") (pintype "bidirectional"))
      (node (ref "U2") (pin "20") (pinfunction "DQ6_20") (pintype "output"))
    )
    (net (code "63") (name "D7") (class "Default")
      (node (ref "1A") (pin "1") (pinfunction "P_1") (pintype "passive"))
      (node (ref "U$1") (pin "P21") (pinfunction "IO_L42N_GCLK24_3_P21") (pintype "bidirectional"))
      (node (ref "U2") (pin "21") (pinfunction "DQ7_21") (pintype "output"))
    )
    (net (code "64") (name "DI_LLS") (class "Default")
      (node (ref "MICRO_SD1") (pin "3") (pinfunction "CMD_3") (pintype "bidirectional"))
      (node (ref "R17") (pin "2") (pinfunction "2_2") (pintype "passive"))
    )
    (net (code "65") (name "DOWN") (class "Default")
      (node (ref "J2") (pin "2") (pinfunction "2_2") (pintype "passive"))
      (node (ref "U$1") (pin "P79") (pinfunction "IO_L47P_1_P79") (pintype "bidirectional"))
    )
    (net (code "66") (name "EN_M1_NOT") (class "Default")
      (node (ref "U$1") (pin "P140") (pinfunction "IO_L3P_0_P140") (pintype "bidirectional"))
      (node (ref "U3") (pin "25") (pinfunction "PA2_25") (pintype "bidirectional"))
    )
    (net (code "67") (name "FIRE") (class "Default")
      (node (ref "J2") (pin "6") (pinfunction "6_6") (pintype "passive"))
      (node (ref "U$1") (pin "P82") (pinfunction "IO_L45N_1_P82") (pintype "bidirectional"))
    )
    (net (code "68") (name "FLASH_CS") (class "Default")
      (node (ref "U$1") (pin "P38") (pinfunction "IO_L65N_CSO_B_2_P38") (pintype "bidirectional"))
      (node (ref "U4") (pin "1") (pinfunction "CS_1") (pintype "bidirectional"))
    )
    (net (code "69") (name "FLASH_MISO") (class "Default")
      (node (ref "U$1") (pin "P65") (pinfunction "IO_L3P_D0_DIN_MISO_MISO1_2_P65") (pintype "bidirectional"))
      (node (ref "U4") (pin "2") (pinfunction "MISO_2") (pintype "bidirectional"))
    )
    (net (code "70") (name "FLASH_MOSI") (class "Default")
      (node (ref "U$1") (pin "P64") (pinfunction "IO_L3N_MOSI_CSI_B_MISO0_2_P64") (pintype "bidirectional"))
      (node (ref "U4") (pin "5") (pinfunction "MOSI_5") (pintype "bidirectional"))
    )
    (net (code "71") (name "FLASH_SCLK") (class "Default")
      (node (ref "U$1") (pin "P70") (pinfunction "IO_L1P_CCLK_2_P70") (pintype "bidirectional"))
      (node (ref "U4") (pin "6") (pinfunction "SCK_6") (pintype "bidirectional"))
    )
    (net (code "72") (name "GET_CTRL_REG") (class "Default")
      (node (ref "U$1") (pin "P5") (pinfunction "IO_L52N_3_P5") (pintype "bidirectional"))
      (node (ref "U3") (pin "66") (pinfunction "PC9_66") (pintype "bidirectional"))
    )
    (net (code "73") (name "GET_DATA_REG") (class "Default")
      (node (ref "U$1") (pin "P2") (pinfunction "IO_L83P_3_P2") (pintype "bidirectional"))
      (node (ref "U3") (pin "78") (pinfunction "PC10_78") (pintype "bidirectional"))
    )
    (net (code "74") (name "GND") (class "Default")
      (node (ref "4B") (pin "1") (pinfunction "P_1") (pintype "passive"))
      (node (ref "5B") (pin "1") (pinfunction "P_1") (pintype "passive"))
      (node (ref "C1") (pin "2") (pinfunction "2_2") (pintype "passive"))
      (node (ref "C10") (pin "2") (pinfunction "2_2") (pintype "passive"))
      (node (ref "C11") (pin "1") (pinfunction "1_1") (pintype "passive"))
      (node (ref "C12") (pin "1") (pinfunction "1_1") (pintype "passive"))
      (node (ref "C18") (pin "2") (pinfunction "2_2") (pintype "passive"))
      (node (ref "C19") (pin "2") (pinfunction "2_2") (pintype "passive"))
      (node (ref "C2") (pin "2") (pinfunction "2_2") (pintype "passive"))
      (node (ref "C22") (pin "1") (pinfunction "1_1") (pintype "passive"))
      (node (ref "C23") (pin "1") (pinfunction "1_1") (pintype "passive"))
      (node (ref "C24") (pin "2") (pinfunction "2_2") (pintype "passive"))
      (node (ref "C25") (pin "2") (pinfunction "2_2") (pintype "passive"))
      (node (ref "C26") (pin "2") (pinfunction "2_2") (pintype "passive"))
      (node (ref "C3") (pin "2") (pinfunction "2_2") (pintype "passive"))
      (node (ref "C33") (pin "2") (pinfunction "2_2") (pintype "passive"))
      (node (ref "C4") (pin "1") (pinfunction "1_1") (pintype "passive"))
      (node (ref "C5") (pin "1") (pinfunction "1_1") (pintype "passive"))
      (node (ref "C7") (pin "2") (pinfunction "2_2") (pintype "passive"))
      (node (ref "IC10") (pin "2") (pinfunction "VSS_2") (pintype "passive"))
      (node (ref "IC10") (pin "6") (pinfunction "A0_6") (pintype "passive"))
      (node (ref "IC2") (pin "1") (pinfunction "GND_1") (pintype "power_in"))
      (node (ref "IC5") (pin "1") (pinfunction "GND_1") (pintype "power_in"))
      (node (ref "J2") (pin "8") (pinfunction "8_8") (pintype "passive"))
      (node (ref "J3") (pin "A1_B12") (pinfunction "GND_A1_B12") (pintype "power_in"))
      (node (ref "J3") (pin "B1_A12") (pinfunction "GND_B1_A12") (pintype "power_in"))
      (node (ref "J3") (pin "SH1") (pinfunction "SHIELD_SH1") (pintype "passive"))
      (node (ref "J3") (pin "SH2") (pinfunction "SHIELD_SH2") (pintype "passive"))
      (node (ref "J3") (pin "SH3") (pinfunction "SHIELD_SH3") (pintype "passive"))
      (node (ref "J3") (pin "SH4") (pinfunction "SHIELD_SH4") (pintype "passive"))
      (node (ref "JP1") (pin "1") (pinfunction "1_1") (pintype "passive"))
      (node (ref "JP2") (pin "2") (pinfunction "2_2") (pintype "passive"))
      (node (ref "JP4") (pin "2") (pinfunction "2_2") (pintype "passive"))
      (node (ref "JP8") (pin "2") (pinfunction "2_2") (pintype "passive"))
      (node (ref "LED3") (pin "P1") (pinfunction "C_P1") (pintype "passive"))
      (node (ref "LED3") (pin "P2") (pinfunction "C_P2") (pintype "passive"))
      (node (ref "LED3") (pin "P3") (pinfunction "C_P3") (pintype "passive"))
      (node (ref "MICRO_SD1") (pin "6") (pinfunction "VSS_6") (pintype "power_in"))
      (node (ref "MICRO_SD1") (pin "MP1") (pinfunction "SHIELD_MP1") (pintype "power_in"))
      (node (ref "MICRO_SD1") (pin "MP2") (pinfunction "SHIELD_MP2") (pintype "power_in"))
      (node (ref "MICRO_SD1") (pin "MP3") (pinfunction "SHIELD_MP3") (pintype "power_in"))
      (node (ref "MICRO_SD1") (pin "MP4") (pinfunction "SHIELD_MP4") (pintype "power_in"))
      (node (ref "R25") (pin "1") (pinfunction "1_1") (pintype "passive"))
      (node (ref "R30") (pin "1") (pinfunction "1_1") (pintype "passive"))
      (node (ref "S1") (pin "1") (pinfunction "P_1") (pintype "passive"))
      (node (ref "U$1") (pin "P108") (pinfunction "GND_P108") (pintype "bidirectional"))
      (node (ref "U$1") (pin "P113") (pinfunction "GND_P113") (pintype "bidirectional"))
      (node (ref "U$1") (pin "P13") (pinfunction "GND_P13") (pintype "bidirectional"))
      (node (ref "U$1") (pin "P130") (pinfunction "GND_P130") (pintype "bidirectional"))
      (node (ref "U$1") (pin "P136") (pinfunction "GND_P136") (pintype "bidirectional"))
      (node (ref "U$1") (pin "P25") (pinfunction "GND_P25") (pintype "bidirectional"))
      (node (ref "U$1") (pin "P3") (pinfunction "GND_P3") (pintype "bidirectional"))
      (node (ref "U$1") (pin "P49") (pinfunction "GND_P49") (pintype "bidirectional"))
      (node (ref "U$1") (pin "P54") (pinfunction "GND_P54") (pintype "bidirectional"))
      (node (ref "U$1") (pin "P68") (pinfunction "GND_P68") (pintype "bidirectional"))
      (node (ref "U$1") (pin "P73") (pinfunction "SUSPEND_P73") (pintype "bidirectional"))
      (node (ref "U$1") (pin "P77") (pinfunction "GND_P77") (pintype "bidirectional"))
      (node (ref "U$1") (pin "P91") (pinfunction "GND_P91") (pintype "bidirectional"))
      (node (ref "U$1") (pin "P96") (pinfunction "GND_P96") (pintype "bidirectional"))
      (node (ref "U2") (pin "16") (pinfunction "VSS_16") (pintype "output"))
      (node (ref "U3") (pin "10") (pinfunction "VSS_10") (pintype "bidirectional"))
      (node (ref "U3") (pin "20") (pinfunction "VSSA_20") (pintype "bidirectional"))
      (node (ref "U3") (pin "27") (pinfunction "VSS_27") (pintype "bidirectional"))
      (node (ref "U3") (pin "74") (pinfunction "VSS_74") (pintype "bidirectional"))
      (node (ref "U3") (pin "99") (pinfunction "VSS_99") (pintype "bidirectional"))
      (node (ref "U4") (pin "4") (pinfunction "GND_4") (pintype "bidirectional"))
    )
    (net (code "75") (name "LEDB") (class "Default")
      (node (ref "R3") (pin "1") (pinfunction "1_1") (pintype "passive"))
      (node (ref "U3") (pin "79") (pinfunction "PC11_79") (pintype "bidirectional"))
    )
    (net (code "76") (name "LEDG") (class "Default")
      (node (ref "R13") (pin "1") (pinfunction "1_1") (pintype "passive"))
      (node (ref "U3") (pin "17") (pinfunction "PC2_17") (pintype "bidirectional"))
    )
    (net (code "77") (name "LEDR") (class "Default")
      (node (ref "R2") (pin "1") (pinfunction "1_1") (pintype "passive"))
      (node (ref "U3") (pin "80") (pinfunction "PC12_80") (pintype "bidirectional"))
    )
    (net (code "78") (name "LEFT") (class "Default")
      (node (ref "J2") (pin "3") (pinfunction "3_3") (pintype "passive"))
      (node (ref "U$1") (pin "P80") (pinfunction "IO_L46N_1_P80") (pintype "bidirectional"))
    )
    (net (code "79") (name "LE_IL") (class "Default")
      (node (ref "U$1") (pin "P14") (pinfunction "IO_L44N_GCLK20_3_P14") (pintype "bidirectional"))
      (node (ref "U3") (pin "7") (pinfunction "PC13_7") (pintype "bidirectional"))
    )
    (net (code "80") (name "MEM_ACCESS") (class "Default")
      (node (ref "U$1") (pin "P11") (pinfunction "IO_L49N_3_P11") (pintype "bidirectional"))
      (node (ref "U3") (pin "16") (pinfunction "PC1_16") (pintype "bidirectional"))
    )
    (net (code "81") (name "MISO") (class "Default")
      (node (ref "R20") (pin "1") (pinfunction "1_1") (pintype "passive"))
      (node (ref "U3") (pin "31") (pinfunction "PA6_31") (pintype "bidirectional"))
    )
    (net (code "82") (name "MOSI") (class "Default")
      (node (ref "R17") (pin "1") (pinfunction "1_1") (pintype "passive"))
      (node (ref "U3") (pin "32") (pinfunction "PA7_32") (pintype "bidirectional"))
    )
    (net (code "83") (name "Net-(J3-DN1)") (class "Default")
      (node (ref "J3") (pin "A7") (pinfunction "DN1_A7") (pintype "bidirectional"))
      (node (ref "J3") (pin "B7") (pinfunction "DN2_B7") (pintype "bidirectional"))
      (node (ref "R26") (pin "1") (pinfunction "1_1") (pintype "passive"))
    )
    (net (code "84") (name "Net-(J3-DP1)") (class "Default")
      (node (ref "J3") (pin "A6") (pinfunction "DP1_A6") (pintype "bidirectional"))
      (node (ref "J3") (pin "B6") (pinfunction "DP2_B6") (pintype "bidirectional"))
      (node (ref "R22") (pin "1") (pinfunction "1_1") (pintype "passive"))
      (node (ref "R23") (pin "1") (pinfunction "1_1") (pintype "passive"))
    )
    (net (code "85") (name "Net-(JP7-Pad1)") (class "Default")
      (node (ref "JP7") (pin "1") (pinfunction "1_1") (pintype "passive"))
      (node (ref "R24") (pin "2") (pinfunction "2_2") (pintype "passive"))
    )
    (net (code "86") (name "Net-(JP7-Pad3)") (class "Default")
      (node (ref "JP7") (pin "3") (pinfunction "3_3") (pintype "passive"))
      (node (ref "R16") (pin "1") (pinfunction "1_1") (pintype "passive"))
    )
    (net (code "87") (name "Net-(LED2-PadA)") (class "Default")
      (node (ref "LED2") (pin "A") (pinfunction "A_A") (pintype "passive"))
      (node (ref "R11") (pin "2") (pinfunction "2_2") (pintype "passive"))
    )
    (net (code "88") (name "Net-(LED3A-A)") (class "Default")
      (node (ref "LED3") (pin "P6") (pinfunction "A_P6") (pintype "passive"))
      (node (ref "R3") (pin "2") (pinfunction "2_2") (pintype "passive"))
    )
    (net (code "89") (name "Net-(LED3B-A)") (class "Default")
      (node (ref "LED3") (pin "P5") (pinfunction "A_P5") (pintype "passive"))
      (node (ref "R13") (pin "2") (pinfunction "2_2") (pintype "passive"))
    )
    (net (code "90") (name "Net-(LED3C-A)") (class "Default")
      (node (ref "LED3") (pin "P4") (pinfunction "A_P4") (pintype "passive"))
      (node (ref "R2") (pin "2") (pinfunction "2_2") (pintype "passive"))
    )
    (net (code "91") (name "Net-(MICRO_SD1-DAT0)") (class "Default")
      (node (ref "MICRO_SD1") (pin "7") (pinfunction "DAT0_7") (pintype "bidirectional"))
      (node (ref "R20") (pin "2") (pinfunction "2_2") (pintype "passive"))
    )
    (net (code "92") (name "Net-(Q3-2)") (class "Default")
      (node (ref "C12") (pin "2") (pinfunction "2_2") (pintype "passive"))
      (node (ref "Q3") (pin "3") (pinfunction "2_3") (pintype "passive"))
      (node (ref "R14") (pin "2") (pinfunction "2_2") (pintype "passive"))
      (node (ref "U3") (pin "13") (pinfunction "PH1_13") (pintype "bidirectional"))
    )
    (net (code "93") (name "Net-(U$1-PROGRAM_B_2)") (class "Default")
      (node (ref "R12") (pin "2") (pinfunction "2_2") (pintype "passive"))
      (node (ref "U$1") (pin "P37") (pinfunction "PROGRAM_B_2_P37") (pintype "bidirectional"))
    )
    (net (code "94") (name "Net-(U3-PC14)") (class "Default")
      (node (ref "C22") (pin "2") (pinfunction "2_2") (pintype "passive"))
      (node (ref "Q4") (pin "2") (pinfunction "2_2") (pintype "passive"))
      (node (ref "U3") (pin "8") (pinfunction "PC14_8") (pintype "bidirectional"))
    )
    (net (code "95") (name "Net-(U3-PC15)") (class "Default")
      (node (ref "C23") (pin "2") (pinfunction "2_2") (pintype "passive"))
      (node (ref "Q4") (pin "1") (pinfunction "1_1") (pintype "passive"))
      (node (ref "U3") (pin "9") (pinfunction "PC15_9") (pintype "bidirectional"))
    )
    (net (code "96") (name "Net-(U3-PH0)") (class "Default")
      (node (ref "C11") (pin "2") (pinfunction "2_2") (pintype "passive"))
      (node (ref "Q3") (pin "1") (pinfunction "1_1") (pintype "passive"))
      (node (ref "R14") (pin "1") (pinfunction "1_1") (pintype "passive"))
      (node (ref "U3") (pin "12") (pinfunction "PH0_12") (pintype "bidirectional"))
    )
    (net (code "97") (name "Net-(U3-VCAP_1)") (class "Default")
      (node (ref "C10") (pin "1") (pinfunction "1_1") (pintype "passive"))
      (node (ref "U3") (pin "49") (pinfunction "VCAP_1_49") (pintype "bidirectional"))
    )
    (net (code "98") (name "Net-(U3-VCAP_2)") (class "Default")
      (node (ref "C7") (pin "1") (pinfunction "1_1") (pintype "passive"))
      (node (ref "U3") (pin "73") (pinfunction "VCAP_2_73") (pintype "bidirectional"))
    )
    (net (code "99") (name "O0") (class "Default")
      (node (ref "U$1") (pin "P126") (pinfunction "IO_L36N_GCLK14_0_P126") (pintype "bidirectional"))
      (node (ref "U3") (pin "81") (pinfunction "PD0_81") (pintype "bidirectional"))
    )
    (net (code "100") (name "O1") (class "Default")
      (node (ref "U$1") (pin "P127") (pinfunction "IO_L36P_GCLK15_0_P127") (pintype "bidirectional"))
      (node (ref "U3") (pin "82") (pinfunction "PD1_82") (pintype "bidirectional"))
    )
    (net (code "101") (name "O2") (class "Default")
      (node (ref "U$1") (pin "P131") (pinfunction "IO_L35N_GCLK16_0_P131") (pintype "bidirectional"))
      (node (ref "U3") (pin "83") (pinfunction "PD2_83") (pintype "bidirectional"))
    )
    (net (code "102") (name "O3") (class "Default")
      (node (ref "U$1") (pin "P132") (pinfunction "IO_L35P_GCLK17_0_P132") (pintype "bidirectional"))
      (node (ref "U3") (pin "84") (pinfunction "PD3_84") (pintype "bidirectional"))
    )
    (net (code "103") (name "O4") (class "Default")
      (node (ref "U$1") (pin "P133") (pinfunction "IO_L34N_GCLK18_0_P133") (pintype "bidirectional"))
      (node (ref "U3") (pin "85") (pinfunction "PD4_85") (pintype "bidirectional"))
    )
    (net (code "104") (name "O5") (class "Default")
      (node (ref "U$1") (pin "P134") (pinfunction "IO_L34P_GCLK19_0_P134") (pintype "bidirectional"))
      (node (ref "U3") (pin "86") (pinfunction "PD5_86") (pintype "bidirectional"))
    )
    (net (code "105") (name "O6") (class "Default")
      (node (ref "U$1") (pin "P137") (pinfunction "IO_L4N_0_P137") (pintype "bidirectional"))
      (node (ref "U3") (pin "87") (pinfunction "PD6_87") (pintype "bidirectional"))
    )
    (net (code "106") (name "O7") (class "Default")
      (node (ref "U$1") (pin "P138") (pinfunction "IO_L4P_0_P138") (pintype "bidirectional"))
      (node (ref "U3") (pin "88") (pinfunction "PD7_88") (pintype "bidirectional"))
    )
    (net (code "107") (name "PA11{slash}USB_DN") (class "Default")
      (node (ref "R26") (pin "2") (pinfunction "2_2") (pintype "passive"))
      (node (ref "U3") (pin "70") (pinfunction "PA11_70") (pintype "bidirectional"))
    )
    (net (code "108") (name "PA12{slash}USB_DP") (class "Default")
      (node (ref "R23") (pin "2") (pinfunction "2_2") (pintype "passive"))
      (node (ref "U3") (pin "71") (pinfunction "PA12_71") (pintype "bidirectional"))
    )
    (net (code "109") (name "PA13{slash}JTMS{slash}SWDIO") (class "Default")
      (node (ref "JP8") (pin "1") (pinfunction "1_1") (pintype "passive"))
      (node (ref "U3") (pin "72") (pinfunction "PA13_72") (pintype "bidirectional"))
    )
    (net (code "110") (name "PA14{slash}JTCK{slash}SWCLK") (class "Default")
      (node (ref "JP8") (pin "3") (pinfunction "3_3") (pintype "passive"))
      (node (ref "U3") (pin "76") (pinfunction "PA14_76") (pintype "bidirectional"))
    )
    (net (code "111") (name "PAGE_A8") (class "Default")
      (node (ref "U$1") (pin "P143") (pinfunction "IO_L1N_VREF_0_P143") (pintype "bidirectional"))
      (node (ref "U3") (pin "24") (pinfunction "PA1_24") (pintype "bidirectional"))
    )
    (net (code "112") (name "PB2{slash}BOOT1") (class "Default")
      (node (ref "R16") (pin "2") (pinfunction "2_2") (pintype "passive"))
      (node (ref "R25") (pin "2") (pinfunction "2_2") (pintype "passive"))
      (node (ref "U3") (pin "37") (pinfunction "PB2_37") (pintype "bidirectional"))
    )
    (net (code "113") (name "RESET") (class "Default")
      (node (ref "C5") (pin "2") (pinfunction "2_2") (pintype "passive"))
      (node (ref "D1") (pin "A") (pinfunction "A_A") (pintype "passive"))
      (node (ref "R15") (pin "1") (pinfunction "1_1") (pintype "passive"))
      (node (ref "S1") (pin "2") (pinfunction "S_2") (pintype "passive"))
      (node (ref "U3") (pin "14") (pinfunction "NRST_14") (pintype "bidirectional"))
    )
    (net (code "114") (name "RIGHT") (class "Default")
      (node (ref "J2") (pin "4") (pinfunction "4_4") (pintype "passive"))
      (node (ref "U$1") (pin "P81") (pinfunction "IO_L46P_1_P81") (pintype "bidirectional"))
    )
    (net (code "115") (name "ROM_WR_EN") (class "Default")
      (node (ref "U$1") (pin "P142") (pinfunction "IO_L2P_0_P142") (pintype "bidirectional"))
      (node (ref "U3") (pin "67") (pinfunction "PA8_67") (pintype "bidirectional"))
    )
    (net (code "116") (name "RST_CTRL_REG") (class "Default")
      (node (ref "U$1") (pin "P1") (pinfunction "IO_L83N_VREF_3_P1") (pintype "bidirectional"))
      (node (ref "U3") (pin "53") (pinfunction "PB14_53") (pintype "bidirectional"))
    )
    (net (code "117") (name "RST_DATA_REG") (class "Default")
      (node (ref "U$1") (pin "P144") (pinfunction "IO_L1P_HSWAPEN_0_P144") (pintype "bidirectional"))
      (node (ref "U3") (pin "91") (pinfunction "PB5_91") (pintype "bidirectional"))
    )
    (net (code "118") (name "SCK_LLS") (class "Default")
      (node (ref "MICRO_SD1") (pin "5") (pinfunction "CLK_5") (pintype "bidirectional"))
      (node (ref "R18") (pin "2") (pinfunction "2_2") (pintype "passive"))
    )
    (net (code "119") (name "SCL") (class "Default")
      (node (ref "IC10") (pin "5") (pinfunction "SCL_5") (pintype "passive"))
      (node (ref "U3") (pin "92") (pinfunction "PB6_92") (pintype "bidirectional"))
    )
    (net (code "120") (name "SCLK") (class "Default")
      (node (ref "R18") (pin "1") (pinfunction "1_1") (pintype "passive"))
      (node (ref "U3") (pin "30") (pinfunction "PA5_30") (pintype "bidirectional"))
    )
    (net (code "121") (name "SDA") (class "Default")
      (node (ref "IC10") (pin "4") (pinfunction "SDA_4") (pintype "passive"))
      (node (ref "U3") (pin "93") (pinfunction "PB7_93") (pintype "bidirectional"))
    )
    (net (code "122") (name "SD_LED") (class "Default")
      (node (ref "LED2") (pin "C") (pinfunction "C_C") (pintype "passive"))
      (node (ref "U3") (pin "29") (pinfunction "PA4_29") (pintype "bidirectional"))
    )
    (net (code "123") (name "SEL_128CHARS") (class "Default")
      (node (ref "U$1") (pin "P141") (pinfunction "IO_L2N_0_P141") (pintype "bidirectional"))
      (node (ref "U3") (pin "77") (pinfunction "PA15_77") (pintype "bidirectional"))
    )
    (net (code "124") (name "SPARE1") (class "Default")
      (node (ref "JP5") (pin "4") (pinfunction "4_4") (pintype "passive"))
      (node (ref "U$1") (pin "P7") (pinfunction "IO_L51N_3_P7") (pintype "bidirectional"))
      (node (ref "U3") (pin "18") (pinfunction "PC3_18") (pintype "bidirectional"))
    )
    (net (code "125") (name "SPARE2") (class "Default")
      (node (ref "JP5") (pin "3") (pinfunction "3_3") (pintype "passive"))
      (node (ref "U$1") (pin "P8") (pinfunction "IO_L51P_3_P8") (pintype "bidirectional"))
      (node (ref "U3") (pin "33") (pinfunction "PC4_33") (pintype "bidirectional"))
    )
    (net (code "126") (name "SPARE3") (class "Default")
      (node (ref "JP5") (pin "2") (pinfunction "2_2") (pintype "passive"))
      (node (ref "U$1") (pin "P9") (pinfunction "IO_L50N_3_P9") (pintype "bidirectional"))
      (node (ref "U3") (pin "34") (pinfunction "PC5_34") (pintype "bidirectional"))
    )
    (net (code "127") (name "SPARE4") (class "Default")
      (node (ref "JP5") (pin "1") (pinfunction "1_1") (pintype "passive"))
      (node (ref "U$1") (pin "P10") (pinfunction "IO_L50P_3_P10") (pintype "bidirectional"))
      (node (ref "U3") (pin "63") (pinfunction "PC6_63") (pintype "bidirectional"))
    )
    (net (code "128") (name "SPEAKER") (class "Default")
      (node (ref "IC10") (pin "1") (pinfunction "VOUT_1") (pintype "passive"))
      (node (ref "JP1") (pin "2") (pinfunction "2_2") (pintype "passive"))
    )
    (net (code "129") (name "SS_SD") (class "Default")
      (node (ref "R21") (pin "1") (pinfunction "1_1") (pintype "passive"))
      (node (ref "U3") (pin "54") (pinfunction "PB15_54") (pintype "bidirectional"))
    )
    (net (code "130") (name "TCK") (class "Default")
      (node (ref "JP3") (pin "1") (pinfunction "1_1") (pintype "passive"))
      (node (ref "U$1") (pin "P109") (pinfunction "TCK_P109") (pintype "bidirectional"))
    )
    (net (code "131") (name "TDI") (class "Default")
      (node (ref "JP3") (pin "3") (pinfunction "3_3") (pintype "passive"))
      (node (ref "U$1") (pin "P110") (pinfunction "TDI_P110") (pintype "bidirectional"))
    )
    (net (code "132") (name "TDO") (class "Default")
      (node (ref "JP3") (pin "2") (pinfunction "2_2") (pintype "passive"))
      (node (ref "U$1") (pin "P106") (pinfunction "TDO_P106") (pintype "bidirectional"))
    )
    (net (code "133") (name "TMS") (class "Default")
      (node (ref "JP3") (pin "4") (pinfunction "4_4") (pintype "passive"))
      (node (ref "U$1") (pin "P107") (pinfunction "TMS_P107") (pintype "bidirectional"))
    )
    (net (code "134") (name "UART_RX") (class "Default")
      (node (ref "JP4") (pin "3") (pinfunction "3_3") (pintype "passive"))
      (node (ref "U3") (pin "69") (pinfunction "PA10_69") (pintype "bidirectional"))
    )
    (net (code "135") (name "UART_TX") (class "Default")
      (node (ref "JP4") (pin "4") (pinfunction "4_4") (pintype "passive"))
      (node (ref "U3") (pin "68") (pinfunction "PA9_68") (pintype "bidirectional"))
    )
    (net (code "136") (name "UP") (class "Default")
      (node (ref "J2") (pin "1") (pinfunction "1_1") (pintype "passive"))
      (node (ref "U$1") (pin "P78") (pinfunction "IO_L47N_1_P78") (pintype "bidirectional"))
    )
    (net (code "137") (name "VCC") (class "Default")
      (node (ref "1B") (pin "1") (pinfunction "P_1") (pintype "passive"))
      (node (ref "C1") (pin "1") (pinfunction "1_1") (pintype "passive"))
      (node (ref "C19") (pin "1") (pinfunction "1_1") (pintype "passive"))
      (node (ref "C2") (pin "1") (pinfunction "1_1") (pintype "passive"))
      (node (ref "C3") (pin "1") (pinfunction "1_1") (pintype "passive"))
      (node (ref "D1") (pin "C") (pinfunction "C_C") (pintype "passive"))
      (node (ref "IC10") (pin "3") (pinfunction "VDD_3") (pintype "passive"))
      (node (ref "IC2") (pin "3") (pinfunction "VIN_3") (pintype "input"))
      (node (ref "IC5") (pin "3") (pinfunction "VIN_3") (pintype "input"))
      (node (ref "JP4") (pin "1") (pinfunction "1_1") (pintype "passive"))
      (node (ref "JP6") (pin "2") (pinfunction "2_2") (pintype "passive"))
      (node (ref "R11") (pin "1") (pinfunction "1_1") (pintype "passive"))
      (node (ref "R15") (pin "2") (pinfunction "2_2") (pintype "passive"))
      (node (ref "R22") (pin "2") (pinfunction "2_2") (pintype "passive"))
      (node (ref "U2") (pin "32") (pinfunction "VCC_32") (pintype "power_in"))
    )
    (net (code "138") (name "VCC_USB") (class "Default")
      (node (ref "J3") (pin "A4_B9") (pinfunction "VBUS_A4_B9") (pintype "power_in"))
      (node (ref "J3") (pin "B4_A9") (pinfunction "VBUS_B4_A9") (pintype "power_in"))
      (node (ref "JP6") (pin "1") (pinfunction "1_1") (pintype "passive"))
    )
    (net (code "139") (name "unconnected-(J2-Pad5)") (class "Default")
      (node (ref "J2") (pin "5") (pinfunction "5_5") (pintype "passive"))
    )
    (net (code "140") (name "unconnected-(J2-Pad7)") (class "Default")
      (node (ref "J2") (pin "7") (pinfunction "7_7") (pintype "passive"))
    )
    (net (code "141") (name "unconnected-(J2-Pad9)") (class "Default")
      (node (ref "J2") (pin "9") (pinfunction "9_9") (pintype "passive"))
    )
    (net (code "142") (name "unconnected-(MICRO_SD1-CD-PadCD1)") (class "Default")
      (node (ref "MICRO_SD1") (pin "CD1") (pinfunction "CD_CD1") (pintype "passive"))
    )
    (net (code "143") (name "unconnected-(MICRO_SD1-DAT1-Pad8)") (class "Default")
      (node (ref "MICRO_SD1") (pin "8") (pinfunction "DAT1_8") (pintype "bidirectional"))
    )
    (net (code "144") (name "unconnected-(MICRO_SD1-DAT2-Pad1)") (class "Default")
      (node (ref "MICRO_SD1") (pin "1") (pinfunction "DAT2_1") (pintype "bidirectional"))
    )
    (net (code "145") (name "unconnected-(U$1-CMPCS_B_2-PadP72)") (class "Default")
      (node (ref "U$1") (pin "P72") (pinfunction "CMPCS_B_2_P72") (pintype "bidirectional"))
    )
    (net (code "146") (name "unconnected-(U$1-DONE_2-PadP71)") (class "Default")
      (node (ref "U$1") (pin "P71") (pinfunction "DONE_2_P71") (pintype "bidirectional"))
    )
    (net (code "147") (name "unconnected-(U3-PA3-Pad26)") (class "Default")
      (node (ref "U3") (pin "26") (pinfunction "PA3_26") (pintype "bidirectional"))
    )
    (net (code "148") (name "unconnected-(U3-PB8-Pad95)") (class "Default")
      (node (ref "U3") (pin "95") (pinfunction "PB8_95") (pintype "bidirectional"))
    )
    (net (code "149") (name "unconnected-(U3-PC7-Pad64)") (class "Default")
      (node (ref "U3") (pin "64") (pinfunction "PC7_64") (pintype "bidirectional"))
    )
    (net (code "150") (name "unconnected-(U3-PC8-Pad65)") (class "Default")
      (node (ref "U3") (pin "65") (pinfunction "PC8_65") (pintype "bidirectional"))
    )
    (net (code "151") (name "{slash}BUSAK") (class "Default")
      (node (ref "18A") (pin "1") (pinfunction "P_1") (pintype "passive"))
    )
    (net (code "152") (name "{slash}BUSRQ") (class "Default")
      (node (ref "20A") (pin "1") (pinfunction "P_1") (pintype "passive"))
    )
    (net (code "153") (name "{slash}CLOCK") (class "Default")
      (node (ref "6B") (pin "1") (pinfunction "P_1") (pintype "passive"))
      (node (ref "U$1") (pin "P24") (pinfunction "IO_L41P_GCLK27_3_P24") (pintype "bidirectional"))
    )
    (net (code "154") (name "{slash}HALT") (class "Default")
      (node (ref "13A") (pin "1") (pinfunction "P_1") (pintype "passive"))
      (node (ref "U$1") (pin "P46") (pinfunction "IO_L49P_D3_2_P46") (pintype "bidirectional"))
    )
    (net (code "155") (name "{slash}IORQ") (class "Default")
      (node (ref "15A") (pin "1") (pinfunction "P_1") (pintype "passive"))
      (node (ref "U$1") (pin "P51") (pinfunction "IO_L31P_GCLK31_D14_2_P51") (pintype "bidirectional"))
    )
    (net (code "156") (name "{slash}M1") (class "Default")
      (node (ref "22A") (pin "1") (pinfunction "P_1") (pintype "passive"))
      (node (ref "U$1") (pin "P67") (pinfunction "IO_L2P_CMPCLK_2_P67") (pintype "bidirectional"))
    )
    (net (code "157") (name "{slash}MEM_CE") (class "Default")
      (node (ref "U$1") (pin "P85") (pinfunction "IO_L43P_GCLK5_1_P85") (pintype "bidirectional"))
      (node (ref "U2") (pin "22") (pinfunction "CE_22") (pintype "input"))
    )
    (net (code "158") (name "{slash}MEM_OE") (class "Default")
      (node (ref "U$1") (pin "P92") (pinfunction "IO_L41N_GCLK8_1_P92") (pintype "bidirectional"))
      (node (ref "U2") (pin "24") (pinfunction "OE_24") (pintype "input"))
    )
    (net (code "159") (name "{slash}MREQ") (class "Default")
      (node (ref "14A") (pin "1") (pinfunction "P_1") (pintype "passive"))
      (node (ref "U$1") (pin "P48") (pinfunction "IO_L48P_D7_2_P48") (pintype "bidirectional"))
    )
    (net (code "160") (name "{slash}NMI") (class "Default")
      (node (ref "12A") (pin "1") (pinfunction "P_1") (pintype "passive"))
      (node (ref "U$1") (pin "P44") (pinfunction "IO_L62P_D5_2_P44") (pintype "bidirectional"))
    )
    (net (code "161") (name "{slash}OE_OL") (class "Default")
      (node (ref "U$1") (pin "P12") (pinfunction "IO_L49P_3_P12") (pintype "bidirectional"))
      (node (ref "U3") (pin "47") (pinfunction "PB10_47") (pintype "bidirectional"))
    )
    (net (code "162") (name "{slash}RAMCS") (class "Default")
      (node (ref "2A") (pin "1") (pinfunction "P_1") (pintype "passive"))
      (node (ref "U$1") (pin "P22") (pinfunction "IO_L42P_GCLK25_TRDY2_3_P22") (pintype "bidirectional"))
    )
    (net (code "163") (name "{slash}RD") (class "Default")
      (node (ref "16A") (pin "1") (pinfunction "P_1") (pintype "passive"))
      (node (ref "U$1") (pin "P56") (pinfunction "IO_L30P_GCLK1_D13_2_P56") (pintype "bidirectional"))
    )
    (net (code "164") (name "{slash}RESET") (class "Default")
      (node (ref "21A") (pin "1") (pinfunction "P_1") (pintype "passive"))
      (node (ref "U$1") (pin "P139") (pinfunction "IO_L3N_0_P139") (pintype "bidirectional"))
      (node (ref "U3") (pin "96") (pinfunction "PB9_96") (pintype "bidirectional"))
    )
    (net (code "165") (name "{slash}RFSH") (class "Default")
      (node (ref "23A") (pin "1") (pinfunction "P_1") (pintype "passive"))
      (node (ref "U$1") (pin "P74") (pinfunction "IO_L74N_DOUT_BUSY_1_P74") (pintype "bidirectional"))
    )
    (net (code "166") (name "{slash}ROMCS") (class "Default")
      (node (ref "23B") (pin "1") (pinfunction "P_1") (pintype "passive"))
      (node (ref "U$1") (pin "P75") (pinfunction "IO_L74P_AWAKE_1_P75") (pintype "bidirectional"))
    )
    (net (code "167") (name "{slash}WAIT") (class "Default")
      (node (ref "19A") (pin "1") (pinfunction "P_1") (pintype "passive"))
      (node (ref "U$1") (pin "P61") (pinfunction "IO_L12N_D2_MISO3_2_P61") (pintype "bidirectional"))
      (node (ref "U3") (pin "23") (pinfunction "PA0_23") (pintype "bidirectional"))
    )
    (net (code "168") (name "{slash}WR") (class "Default")
      (node (ref "17A") (pin "1") (pinfunction "P_1") (pintype "passive"))
      (node (ref "U$1") (pin "P58") (pinfunction "IO_L14P_D11_2_P58") (pintype "bidirectional"))
      (node (ref "U3") (pin "15") (pinfunction "PC0_15") (pintype "bidirectional"))
    )
    (net (code "169") (name "{slash}WR'") (class "Default")
      (node (ref "U$1") (pin "P102") (pinfunction "IO_L32P_1_P102") (pintype "bidirectional"))
      (node (ref "U2") (pin "29") (pinfunction "WE_29") (pintype "input"))
    )
  )
)
